# All-in-one_Starter_Kit_for_Arduino_Nano_.net
KiCad netlist of a schematic drawn in EAGLE
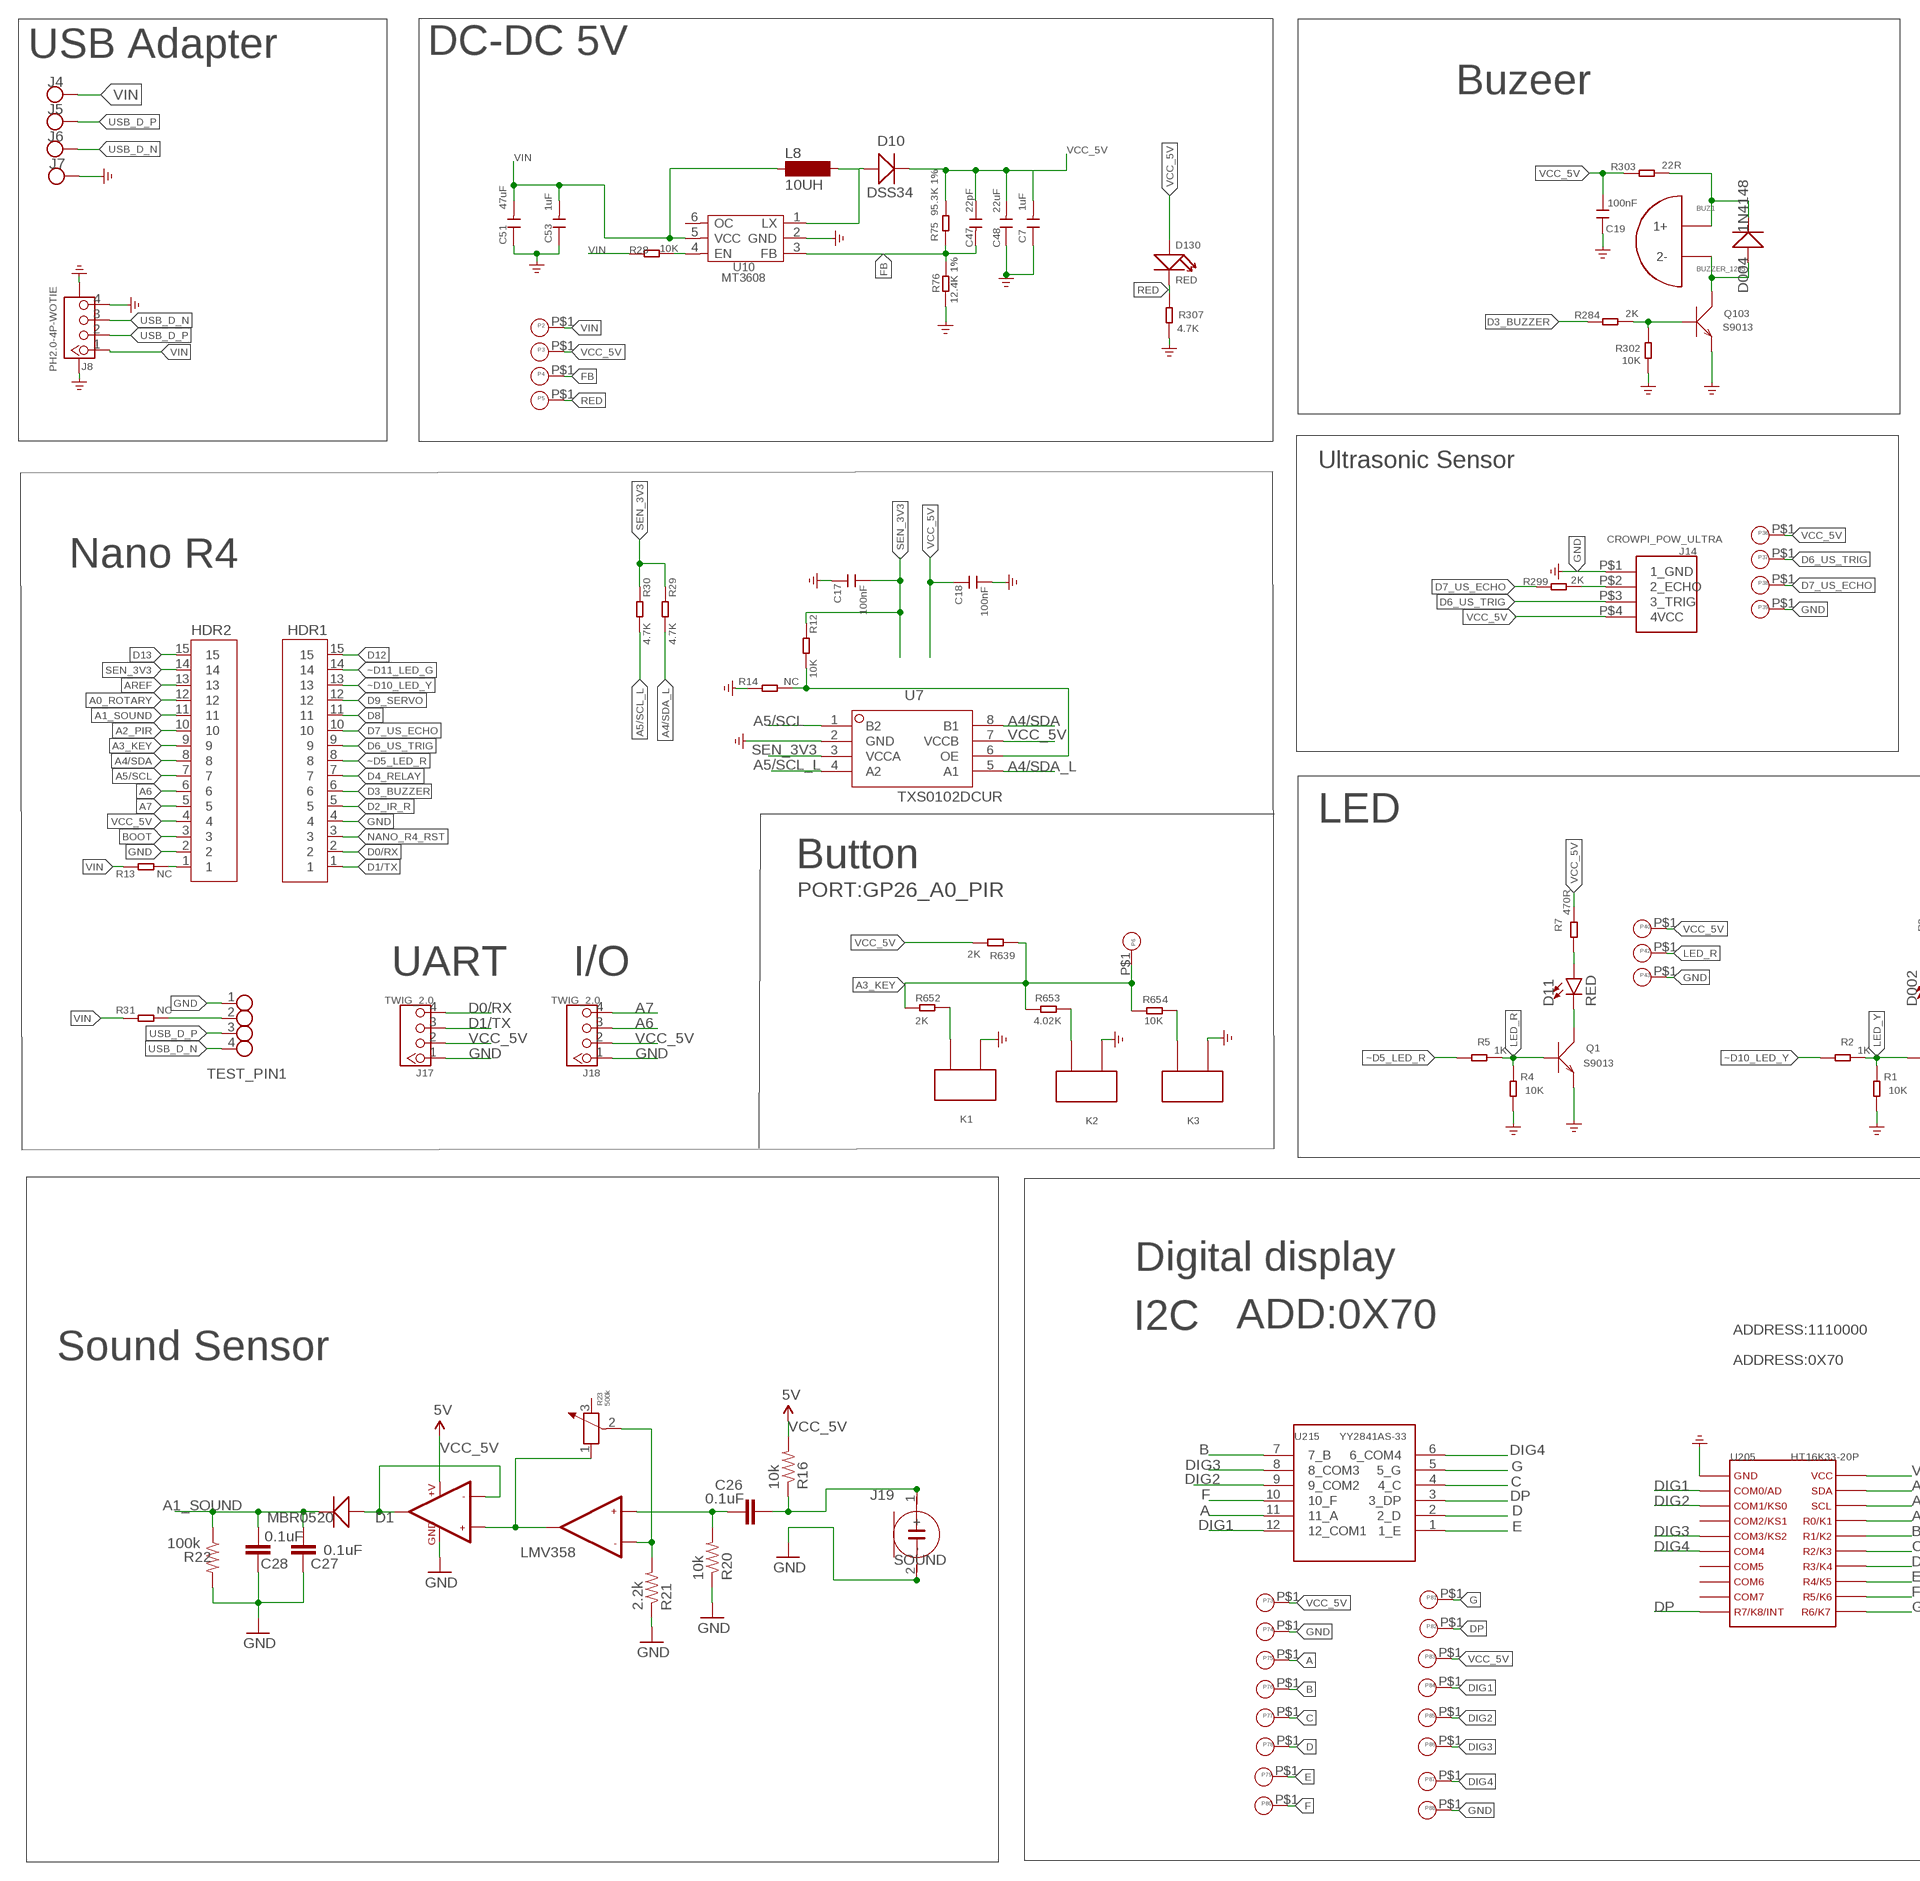
[diagram p0: schematic, sheet 1, part 1 of 2]
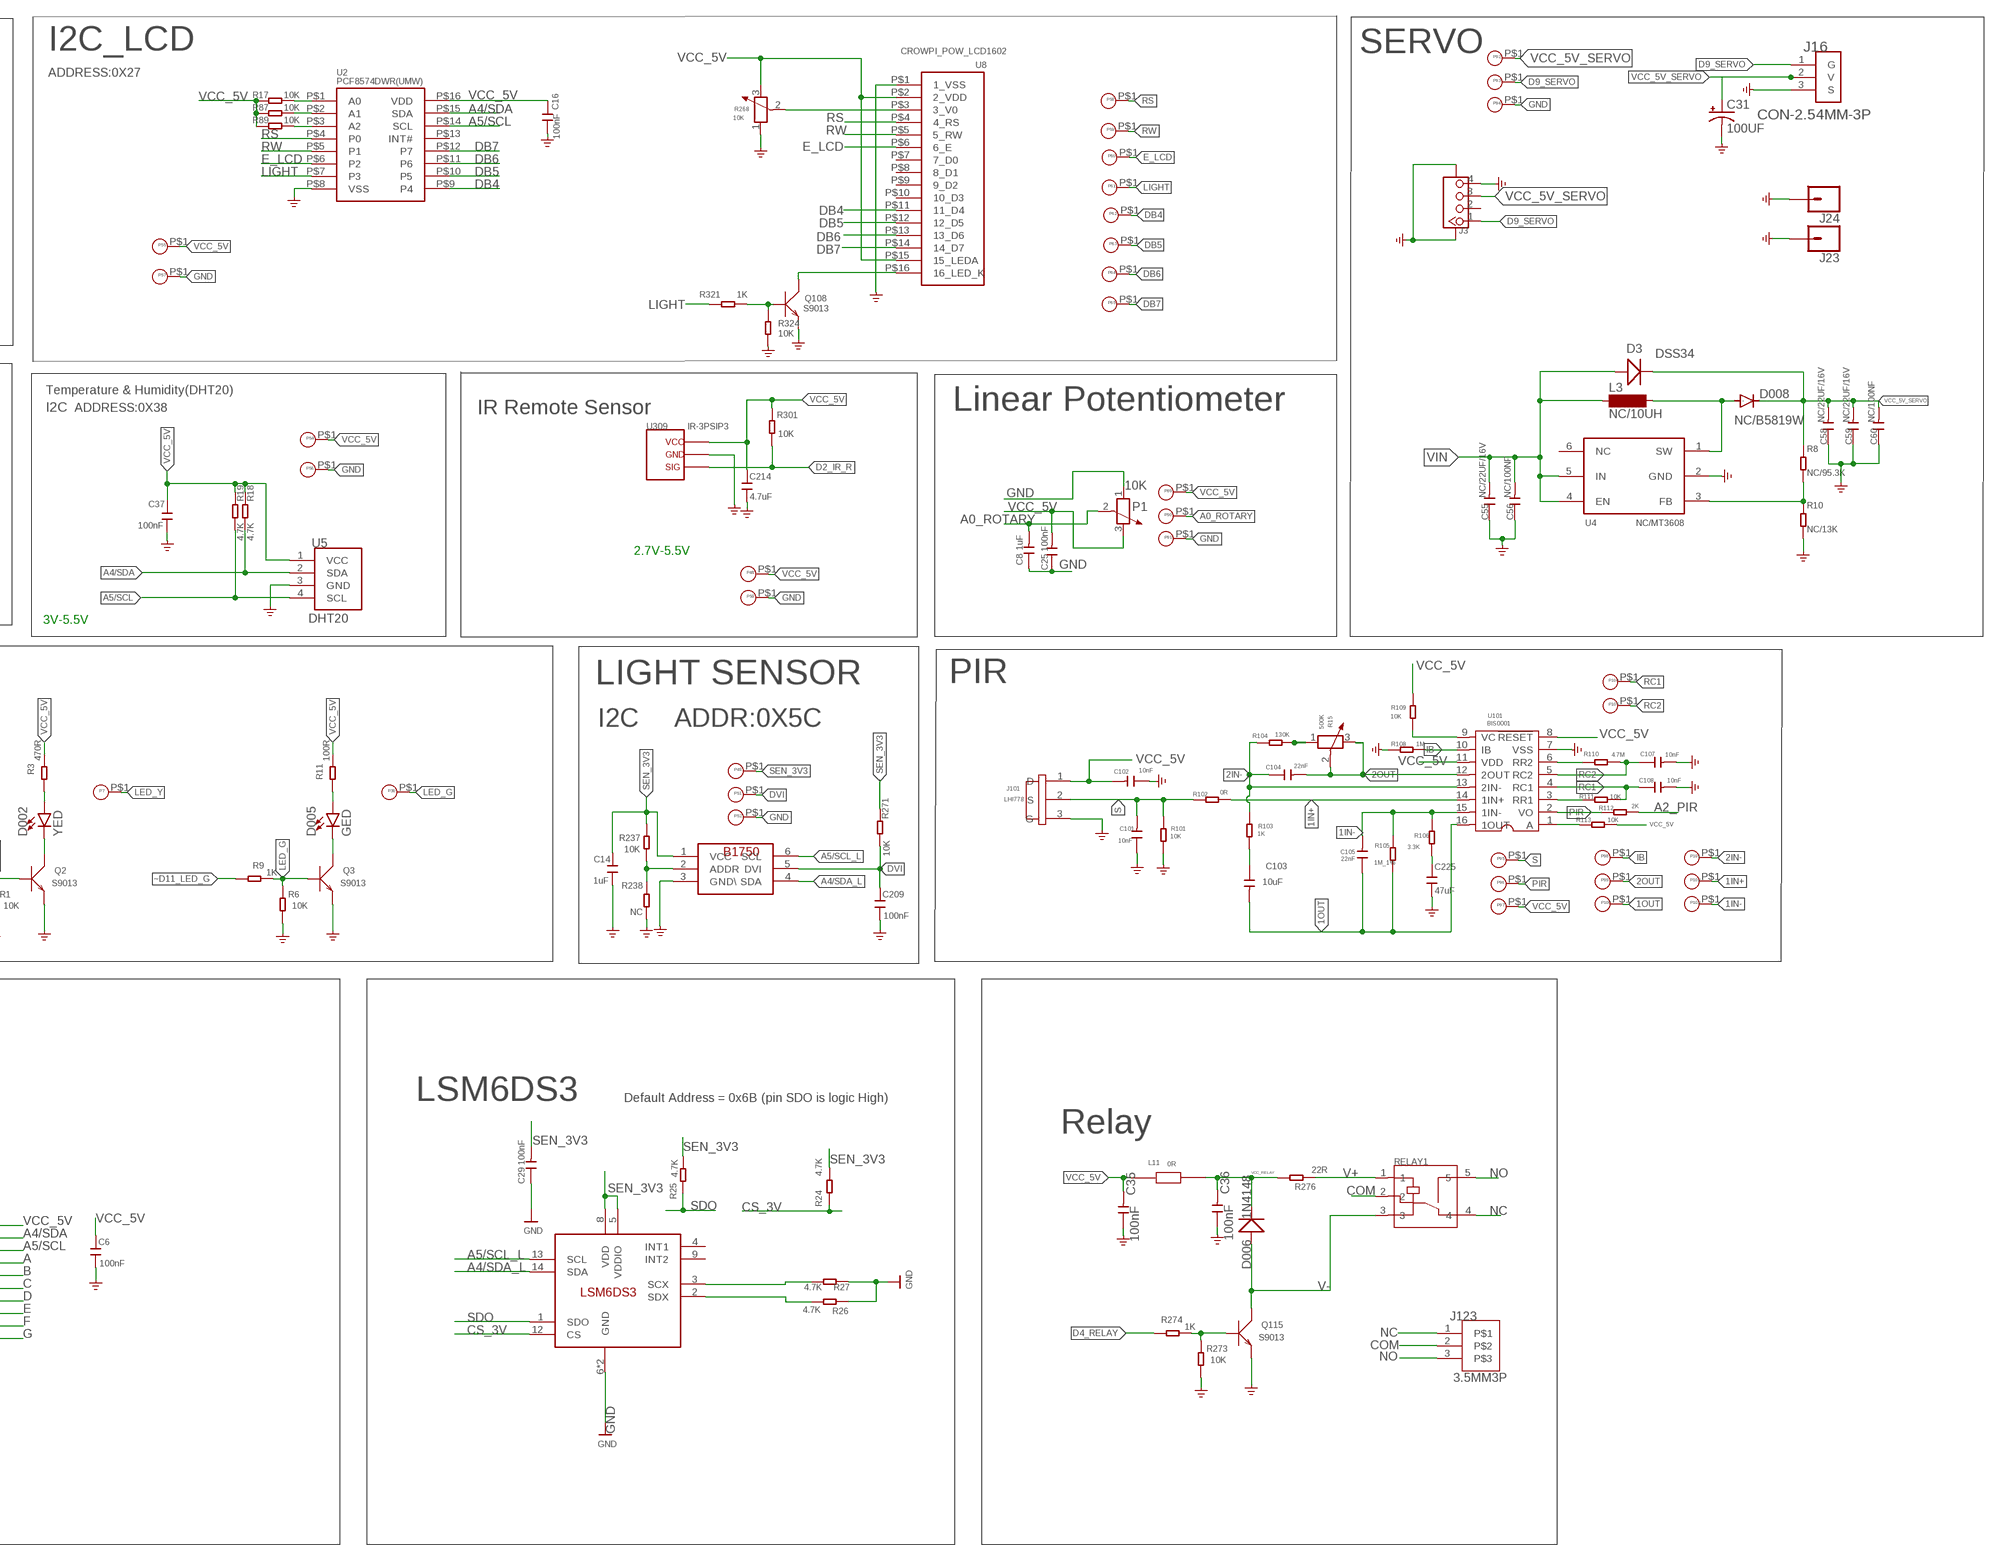
[diagram p1: schematic, sheet 1, part 2 of 2]

(export (version "E")
  (design (tool "Eeschema 10.0.6"))
  (components
    (comp (ref "BUZ1")
      (value "BUZZER_1295")
      (footprint "eagle-import:BUZZER-D12MM-DIP2")
      (libsource (lib "eagle-import") (part "BUZZERBUZZER_1295_DIP"))
    )
    (comp (ref "C6")
      (value "100nF")
      (footprint "eagle-import:0603")
      (libsource (lib "eagle-import") (part "cooper_C0603"))
    )
    (comp (ref "C7")
      (value "1uF")
      (footprint "eagle-import:C0603")
      (libsource (lib "eagle-import") (part "CAP"))
    )
    (comp (ref "C8")
      (value "1uF")
      (footprint "eagle-import:C0603")
      (libsource (lib "eagle-import") (part "C-0603"))
    )
    (comp (ref "C14")
      (value "1uF")
      (footprint "eagle-import:0603")
      (libsource (lib "eagle-import") (part "cooper_C0603"))
    )
    (comp (ref "C16")
      (value "100nF")
      (footprint "eagle-import:0603")
      (libsource (lib "eagle-import") (part "cooper_C0603"))
    )
    (comp (ref "C17")
      (value "100nF")
      (footprint "eagle-import:0603")
      (libsource (lib "eagle-import") (part "cooper_C0603"))
    )
    (comp (ref "C18")
      (value "100nF")
      (footprint "eagle-import:0603")
      (libsource (lib "eagle-import") (part "cooper_C0603"))
    )
    (comp (ref "C19")
      (value "100nF")
      (footprint "eagle-import:0603")
      (libsource (lib "eagle-import") (part "cooper_C0603"))
    )
    (comp (ref "C25")
      (value "100nF")
      (footprint "eagle-import:C0603")
      (libsource (lib "eagle-import") (part "C-0603"))
    )
    (comp (ref "C26")
      (value "0.1uF")
      (footprint "eagle-import:0603-CAP")
      (libsource (lib "eagle-import") (part "CAP0603-CAP"))
    )
    (comp (ref "C27")
      (value "0.1uF")
      (footprint "eagle-import:0603-CAP")
      (libsource (lib "eagle-import") (part "CAP0603-CAP"))
    )
    (comp (ref "C28")
      (value "0.1uF")
      (footprint "eagle-import:0603-CAP")
      (libsource (lib "eagle-import") (part "CAP0603-CAP"))
    )
    (comp (ref "C29")
      (value "100nF")
      (footprint "eagle-import:C0603")
      (libsource (lib "eagle-import") (part "C-0603"))
    )
    (comp (ref "C31")
      (value "100UF")
      (footprint "eagle-import:SANYO-OSCON_SMD_C6")
      (libsource (lib "eagle-import") (part "CPOL-USSANYO_SMD_C6"))
    )
    (comp (ref "C35")
      (value "100nF")
      (footprint "eagle-import:C0603")
      (libsource (lib "eagle-import") (part "C-0603"))
    )
    (comp (ref "C36")
      (value "100nF")
      (footprint "eagle-import:C0603")
      (libsource (lib "eagle-import") (part "C-0603"))
    )
    (comp (ref "C37")
      (value "100nF")
      (footprint "eagle-import:0603")
      (libsource (lib "eagle-import") (part "cooper_C0603"))
    )
    (comp (ref "C47")
      (value "22pF")
      (footprint "eagle-import:C0603")
      (libsource (lib "eagle-import") (part "CAP"))
    )
    (comp (ref "C48")
      (value "22uF")
      (footprint "eagle-import:C0805")
      (libsource (lib "eagle-import") (part "CAPC0805"))
    )
    (comp (ref "C51")
      (value "47uF")
      (footprint "eagle-import:C0805")
      (libsource (lib "eagle-import") (part "CAPC0805"))
    )
    (comp (ref "C53")
      (value "1uF")
      (footprint "eagle-import:C0603")
      (libsource (lib "eagle-import") (part "CAP"))
    )
    (comp (ref "C55")
      (value "NC/22UF/16V")
      (footprint "eagle-import:C0603")
      (libsource (lib "eagle-import") (part "SX1302_Module_CAP"))
    )
    (comp (ref "C56")
      (value "NC/100NF")
      (footprint "eagle-import:C0603")
      (libsource (lib "eagle-import") (part "SX1302_Module_CAP"))
    )
    (comp (ref "C58")
      (value "NC/22UF/16V")
      (footprint "eagle-import:C0603")
      (libsource (lib "eagle-import") (part "SX1302_Module_CAP"))
    )
    (comp (ref "C59")
      (value "NC/22UF/16V")
      (footprint "eagle-import:C0603")
      (libsource (lib "eagle-import") (part "SX1302_Module_CAP"))
    )
    (comp (ref "C60")
      (value "NC/100NF")
      (footprint "eagle-import:C0603")
      (libsource (lib "eagle-import") (part "SX1302_Module_CAP"))
    )
    (comp (ref "C101")
      (value "10nF")
      (footprint "eagle-import:C0603")
      (libsource (lib "eagle-import") (part "C-0603"))
    )
    (comp (ref "C102")
      (value "10nF")
      (footprint "eagle-import:C0603")
      (libsource (lib "eagle-import") (part "C-0603"))
    )
    (comp (ref "C103")
      (value "10uF")
      (footprint "eagle-import:0603")
      (libsource (lib "eagle-import") (part "C0603"))
    )
    (comp (ref "C104")
      (value "22nF")
      (footprint "eagle-import:C0603")
      (libsource (lib "eagle-import") (part "C-0603"))
    )
    (comp (ref "C105")
      (value "22nF")
      (footprint "eagle-import:C0603")
      (libsource (lib "eagle-import") (part "C-0603"))
    )
    (comp (ref "C107")
      (value "10nF")
      (footprint "eagle-import:C0603")
      (libsource (lib "eagle-import") (part "C-0603"))
    )
    (comp (ref "C108")
      (value "10nF")
      (footprint "eagle-import:C0603")
      (libsource (lib "eagle-import") (part "C-0603"))
    )
    (comp (ref "C209")
      (value "100nF")
      (footprint "eagle-import:0603")
      (libsource (lib "eagle-import") (part "cooper_C0603"))
    )
    (comp (ref "C214")
      (value "4.7uF")
      (footprint "eagle-import:0603")
      (libsource (lib "eagle-import") (part "cooper_C0603"))
    )
    (comp (ref "C225")
      (value "47uF")
      (footprint "eagle-import:0805")
      (libsource (lib "eagle-import") (part "C0805"))
    )
    (comp (ref "D1")
      (value "MBR0520")
      (footprint "eagle-import:SOD123-2.7X1.6")
      (libsource (lib "eagle-import") (part "D'MBR0520LT1'"))
    )
    (comp (ref "D002")
      (value "YED")
      (footprint "eagle-import:LED-8MM")
      (libsource (lib "eagle-import") (part "LED"))
    )
    (comp (ref "D3")
      (value "DSS34")
      (footprint "eagle-import:D_SOD123FL")
      (libsource (lib "eagle-import") (part "DIODE"))
    )
    (comp (ref "D004")
      (value "1N4148")
      (footprint "eagle-import:D_SOD123")
      (libsource (lib "eagle-import") (part "Crowtail_Starter_DIODE1206"))
    )
    (comp (ref "D005")
      (value "GED")
      (footprint "eagle-import:LED-8MM")
      (libsource (lib "eagle-import") (part "LED"))
    )
    (comp (ref "D006")
      (value "1N4148")
      (footprint "eagle-import:D_SOD123")
      (libsource (lib "eagle-import") (part "Crowtail_Starter_DIODE1206"))
    )
    (comp (ref "D008")
      (value "NC/B5819W")
      (footprint "eagle-import:SOD-123_MINI-SMA")
      (libsource (lib "eagle-import") (part "CGRM400-G1"))
    )
    (comp (ref "D10")
      (value "DSS34")
      (footprint "eagle-import:D_SOD123FL")
      (libsource (lib "eagle-import") (part "DIODE"))
    )
    (comp (ref "D11")
      (value "RED")
      (footprint "eagle-import:LED-8MM")
      (libsource (lib "eagle-import") (part "LED"))
    )
    (comp (ref "D130")
      (value "RED")
      (footprint "eagle-import:LED_0603_SMT")
      (libsource (lib "eagle-import") (part "LED_0603_SMT"))
    )
    (comp (ref "HDR1")
      (value "KH-2.54FH-1X15P-H8.5")
      (footprint "eagle-import:HDR-TH_15P-P2.54-V-F")
      (libsource (lib "eagle-import") (part "KH-2.54FH-1X15P-H8.5"))
    )
    (comp (ref "HDR2")
      (value "KH-2.54FH-1X15P-H8.5")
      (footprint "eagle-import:HDR-TH_15P-P2.54-V-F")
      (libsource (lib "eagle-import") (part "KH-2.54FH-1X15P-H8.5"))
    )
    (comp (ref "J3")
      (value "A_XBJ_CONNECTOR_TWIG-4P-2.0-SMD-FEMALE-REINFORCE90D")
      (footprint "eagle-import:A_XBJ_CONNECTOR_4P-SMD-2.0-90D")
      (libsource (lib "eagle-import") (part "A_XBJ_CONNECTOR_TWIG-4P-2.0-SMD-FEMALE-REINFORCE90D"))
    )
    (comp (ref "J4")
      (value "TP-SMDTP-SMD-2X4MM")
      (footprint "eagle-import:TP-SMD-2X4MM")
      (libsource (lib "eagle-import") (part "TP-SMDTP-SMD-2X4MM"))
    )
    (comp (ref "J5")
      (value "TP-SMDTP-SMD-2X4MM")
      (footprint "eagle-import:TP-SMD-2X4MM")
      (libsource (lib "eagle-import") (part "TP-SMDTP-SMD-2X4MM"))
    )
    (comp (ref "J6")
      (value "TP-SMDTP-SMD-2X4MM")
      (footprint "eagle-import:TP-SMD-2X4MM")
      (libsource (lib "eagle-import") (part "TP-SMDTP-SMD-2X4MM"))
    )
    (comp (ref "J7")
      (value "TP-SMDTP-SMD-2X4MM")
      (footprint "eagle-import:TP-SMD-2X4MM")
      (libsource (lib "eagle-import") (part "TP-SMDTP-SMD-2X4MM"))
    )
    (comp (ref "J8")
      (value "PH2.0-4P-WOTIE")
      (footprint "eagle-import:PH2.0-4P")
      (libsource (lib "eagle-import") (part "PH2.0-4P-WOTIE"))
    )
    (comp (ref "J14")
      (value "CROWPI_POW_ULTRA")
      (footprint "eagle-import:CROWPI_POW_ULTRA")
      (libsource (lib "eagle-import") (part "CROWPI_POW_ULTRA"))
    )
    (comp (ref "J16")
      (value "CON-2.54MM-3P")
      (footprint "eagle-import:CON-PZ-2.54MM-1_3P-WT")
      (libsource (lib "eagle-import") (part "CON-2.54MM-13P-WT-SG90"))
    )
    (comp (ref "J17")
      (value "TWIG_2.0")
      (footprint "eagle-import:2.0_1X4")
      (libsource (lib "eagle-import") (part "TWIG_2.0"))
    )
    (comp (ref "J18")
      (value "TWIG_2.0")
      (footprint "eagle-import:2.0_1X4")
      (libsource (lib "eagle-import") (part "TWIG_2.0"))
    )
    (comp (ref "J19")
      (value "SOUND")
      (footprint "eagle-import:TEMPLATE_2P-D8.9MM")
      (libsource (lib "eagle-import") (part "TEMPLATE_MICROPHONE"))
    )
    (comp (ref "J23")
      (value "CONN_01_2.6MM1X01_2.6-4MM")
      (footprint "eagle-import:1X01_2.6MM")
      (libsource (lib "eagle-import") (part "CONN_01_2.6MM1X01_2.6-4MM"))
    )
    (comp (ref "J24")
      (value "CONN_01_2.6MM1X01_2.6-4MM")
      (footprint "eagle-import:1X01_2.6MM")
      (libsource (lib "eagle-import") (part "CONN_01_2.6MM1X01_2.6-4MM"))
    )
    (comp (ref "J101")
      (value "LHI778")
      (footprint "eagle-import:3P-D8.1MM")
      (libsource (lib "eagle-import") (part "LHI778"))
    )
    (comp (ref "J123")
      (value "3.5MM3P")
      (footprint "eagle-import:3.5MM_3P")
      (libsource (lib "eagle-import") (part "3.5MM3P"))
    )
    (comp (ref "K1")
      (value "BUTTON_2P")
      (footprint "eagle-import:BUTTON_2P")
      (libsource (lib "eagle-import") (part "BUTTON_2P"))
    )
    (comp (ref "K2")
      (value "BUTTON_2P")
      (footprint "eagle-import:BUTTON_2P")
      (libsource (lib "eagle-import") (part "BUTTON_2P"))
    )
    (comp (ref "K3")
      (value "BUTTON_2P")
      (footprint "eagle-import:BUTTON_2P")
      (libsource (lib "eagle-import") (part "BUTTON_2P"))
    )
    (comp (ref "L3")
      (value "NC/10UH")
      (footprint "eagle-import:MS42")
      (libsource (lib "eagle-import") (part "MS42"))
    )
    (comp (ref "L8")
      (value "10UH")
      (footprint "eagle-import:MS42")
      (libsource (lib "eagle-import") (part "MS42"))
    )
    (comp (ref "L11")
      (value "0R")
      (footprint "eagle-import:201209")
      (libsource (lib "eagle-import") (part "CMP201209UD1R0MT201209"))
    )
    (comp (ref "P1")
      (value "10K")
      (footprint "eagle-import:3P-SQUA-45.6X10X5.8H")
      (libsource (lib "eagle-import") (part "R-POTENTIOMETER"))
    )
    (comp (ref "P2")
      (value "PADPAD-1.0MM")
      (footprint "eagle-import:PAD-1.0MM")
      (libsource (lib "eagle-import") (part "PADPAD-1.0MM"))
    )
    (comp (ref "P3")
      (value "PADPAD-1.0MM")
      (footprint "eagle-import:PAD-1.0MM")
      (libsource (lib "eagle-import") (part "PADPAD-1.0MM"))
    )
    (comp (ref "P4")
      (value "PADPAD-1.0MM")
      (footprint "eagle-import:PAD-1.0MM")
      (libsource (lib "eagle-import") (part "PADPAD-1.0MM"))
    )
    (comp (ref "P5")
      (value "PADPAD-1.0MM")
      (footprint "eagle-import:PAD-1.0MM")
      (libsource (lib "eagle-import") (part "PADPAD-1.0MM"))
    )
    (comp (ref "P6")
      (value "PADPAD-1.0MM")
      (footprint "eagle-import:PAD-1.0MM")
      (libsource (lib "eagle-import") (part "PADPAD-1.0MM"))
    )
    (comp (ref "P7")
      (value "PADPAD-1.0MM")
      (footprint "eagle-import:PAD-1.0MM")
      (libsource (lib "eagle-import") (part "PADPAD-1.0MM"))
    )
    (comp (ref "P30")
      (value "PADPAD-1.0MM")
      (footprint "eagle-import:PAD-1.0MM")
      (libsource (lib "eagle-import") (part "PADPAD-1.0MM"))
    )
    (comp (ref "P36")
      (value "PADPAD-1.0MM")
      (footprint "eagle-import:PAD-1.0MM")
      (libsource (lib "eagle-import") (part "PADPAD-1.0MM"))
    )
    (comp (ref "P37")
      (value "PADPAD-1.0MM")
      (footprint "eagle-import:PAD-1.0MM")
      (libsource (lib "eagle-import") (part "PADPAD-1.0MM"))
    )
    (comp (ref "P38")
      (value "PADPAD-1.0MM")
      (footprint "eagle-import:PAD-1.0MM")
      (libsource (lib "eagle-import") (part "PADPAD-1.0MM"))
    )
    (comp (ref "P39")
      (value "PADPAD-1.0MM")
      (footprint "eagle-import:PAD-1.0MM")
      (libsource (lib "eagle-import") (part "PADPAD-1.0MM"))
    )
    (comp (ref "P40")
      (value "PADPAD-1.0MM")
      (footprint "eagle-import:PAD-1.0MM")
      (libsource (lib "eagle-import") (part "PADPAD-1.0MM"))
    )
    (comp (ref "P42")
      (value "PADPAD-1.0MM")
      (footprint "eagle-import:PAD-1.0MM")
      (libsource (lib "eagle-import") (part "PADPAD-1.0MM"))
    )
    (comp (ref "P43")
      (value "PADPAD-1.0MM")
      (footprint "eagle-import:PAD-1.0MM")
      (libsource (lib "eagle-import") (part "PADPAD-1.0MM"))
    )
    (comp (ref "P48")
      (value "PADPAD-1.0MM")
      (footprint "eagle-import:PAD-1.0MM")
      (libsource (lib "eagle-import") (part "PADPAD-1.0MM"))
    )
    (comp (ref "P49")
      (value "PADPAD-1.0MM")
      (footprint "eagle-import:PAD-1.0MM")
      (libsource (lib "eagle-import") (part "PADPAD-1.0MM"))
    )
    (comp (ref "P50")
      (value "PADPAD-1.0MM")
      (footprint "eagle-import:PAD-1.0MM")
      (libsource (lib "eagle-import") (part "PADPAD-1.0MM"))
    )
    (comp (ref "P51")
      (value "PADPAD-1.0MM")
      (footprint "eagle-import:PAD-1.0MM")
      (libsource (lib "eagle-import") (part "PADPAD-1.0MM"))
    )
    (comp (ref "P52")
      (value "PADPAD-1.0MM")
      (footprint "eagle-import:PAD-1.0MM")
      (libsource (lib "eagle-import") (part "PADPAD-1.0MM"))
    )
    (comp (ref "P54")
      (value "PADPAD-1.0MM")
      (footprint "eagle-import:PAD-1.0MM")
      (libsource (lib "eagle-import") (part "PADPAD-1.0MM"))
    )
    (comp (ref "P55")
      (value "PADPAD-1.0MM")
      (footprint "eagle-import:PAD-1.0MM")
      (libsource (lib "eagle-import") (part "PADPAD-1.0MM"))
    )
    (comp (ref "P56")
      (value "PADPAD-1.0MM")
      (footprint "eagle-import:PAD-1.0MM")
      (libsource (lib "eagle-import") (part "PADPAD-1.0MM"))
    )
    (comp (ref "P57")
      (value "PADPAD-1.0MM")
      (footprint "eagle-import:PAD-1.0MM")
      (libsource (lib "eagle-import") (part "PADPAD-1.0MM"))
    )
    (comp (ref "P58")
      (value "PADPAD-1.0MM")
      (footprint "eagle-import:PAD-1.0MM")
      (libsource (lib "eagle-import") (part "PADPAD-1.0MM"))
    )
    (comp (ref "P59")
      (value "PADPAD-1.0MM")
      (footprint "eagle-import:PAD-1.0MM")
      (libsource (lib "eagle-import") (part "PADPAD-1.0MM"))
    )
    (comp (ref "P60")
      (value "PADPAD-1.0MM")
      (footprint "eagle-import:PAD-1.0MM")
      (libsource (lib "eagle-import") (part "PADPAD-1.0MM"))
    )
    (comp (ref "P61")
      (value "PADPAD-1.0MM")
      (footprint "eagle-import:PAD-1.0MM")
      (libsource (lib "eagle-import") (part "PADPAD-1.0MM"))
    )
    (comp (ref "P62")
      (value "PADPAD-1.0MM")
      (footprint "eagle-import:PAD-1.0MM")
      (libsource (lib "eagle-import") (part "PADPAD-1.0MM"))
    )
    (comp (ref "P63")
      (value "PADPAD-1.0MM")
      (footprint "eagle-import:PAD-1.0MM")
      (libsource (lib "eagle-import") (part "PADPAD-1.0MM"))
    )
    (comp (ref "P64")
      (value "PADPAD-1.0MM")
      (footprint "eagle-import:PAD-1.0MM")
      (libsource (lib "eagle-import") (part "PADPAD-1.0MM"))
    )
    (comp (ref "P65")
      (value "PADPAD-1.0MM")
      (footprint "eagle-import:PAD-1.0MM")
      (libsource (lib "eagle-import") (part "PADPAD-1.0MM"))
    )
    (comp (ref "P73")
      (value "PADPAD-1.0MM")
      (footprint "eagle-import:PAD-1.0MM")
      (libsource (lib "eagle-import") (part "PADPAD-1.0MM"))
    )
    (comp (ref "P74")
      (value "PADPAD-1.0MM")
      (footprint "eagle-import:PAD-1.0MM")
      (libsource (lib "eagle-import") (part "PADPAD-1.0MM"))
    )
    (comp (ref "P75")
      (value "PADPAD-1.0MM")
      (footprint "eagle-import:PAD-1.0MM")
      (libsource (lib "eagle-import") (part "PADPAD-1.0MM"))
    )
    (comp (ref "P76")
      (value "PADPAD-1.0MM")
      (footprint "eagle-import:PAD-1.0MM")
      (libsource (lib "eagle-import") (part "PADPAD-1.0MM"))
    )
    (comp (ref "P77")
      (value "PADPAD-1.0MM")
      (footprint "eagle-import:PAD-1.0MM")
      (libsource (lib "eagle-import") (part "PADPAD-1.0MM"))
    )
    (comp (ref "P78")
      (value "PADPAD-1.0MM")
      (footprint "eagle-import:PAD-1.0MM")
      (libsource (lib "eagle-import") (part "PADPAD-1.0MM"))
    )
    (comp (ref "P79")
      (value "PADPAD-1.0MM")
      (footprint "eagle-import:PAD-1.0MM")
      (libsource (lib "eagle-import") (part "PADPAD-1.0MM"))
    )
    (comp (ref "P80")
      (value "PADPAD-1.0MM")
      (footprint "eagle-import:PAD-1.0MM")
      (libsource (lib "eagle-import") (part "PADPAD-1.0MM"))
    )
    (comp (ref "P81")
      (value "PADPAD-1.0MM")
      (footprint "eagle-import:PAD-1.0MM")
      (libsource (lib "eagle-import") (part "PADPAD-1.0MM"))
    )
    (comp (ref "P82")
      (value "PADPAD-1.0MM")
      (footprint "eagle-import:PAD-1.0MM")
      (libsource (lib "eagle-import") (part "PADPAD-1.0MM"))
    )
    (comp (ref "P83")
      (value "PADPAD-1.0MM")
      (footprint "eagle-import:PAD-1.0MM")
      (libsource (lib "eagle-import") (part "PADPAD-1.0MM"))
    )
    (comp (ref "P84")
      (value "PADPAD-1.0MM")
      (footprint "eagle-import:PAD-1.0MM")
      (libsource (lib "eagle-import") (part "PADPAD-1.0MM"))
    )
    (comp (ref "P85")
      (value "PADPAD-1.0MM")
      (footprint "eagle-import:PAD-1.0MM")
      (libsource (lib "eagle-import") (part "PADPAD-1.0MM"))
    )
    (comp (ref "P86")
      (value "PADPAD-1.0MM")
      (footprint "eagle-import:PAD-1.0MM")
      (libsource (lib "eagle-import") (part "PADPAD-1.0MM"))
    )
    (comp (ref "P87")
      (value "PADPAD-1.0MM")
      (footprint "eagle-import:PAD-1.0MM")
      (libsource (lib "eagle-import") (part "PADPAD-1.0MM"))
    )
    (comp (ref "P88")
      (value "PADPAD-1.0MM")
      (footprint "eagle-import:PAD-1.0MM")
      (libsource (lib "eagle-import") (part "PADPAD-1.0MM"))
    )
    (comp (ref "P89")
      (value "PADPAD-1.0MM")
      (footprint "eagle-import:PAD-1.0MM")
      (libsource (lib "eagle-import") (part "PADPAD-1.0MM"))
    )
    (comp (ref "P90")
      (value "PADPAD-1.0MM")
      (footprint "eagle-import:PAD-1.0MM")
      (libsource (lib "eagle-import") (part "PADPAD-1.0MM"))
    )
    (comp (ref "P91")
      (value "PADPAD-1.0MM")
      (footprint "eagle-import:PAD-1.0MM")
      (libsource (lib "eagle-import") (part "PADPAD-1.0MM"))
    )
    (comp (ref "P92")
      (value "PADPAD-1.0MM")
      (footprint "eagle-import:PAD-1.0MM")
      (libsource (lib "eagle-import") (part "PADPAD-1.0MM"))
    )
    (comp (ref "P93")
      (value "PADPAD-1.0MM")
      (footprint "eagle-import:PAD-1.0MM")
      (libsource (lib "eagle-import") (part "PADPAD-1.0MM"))
    )
    (comp (ref "P94")
      (value "PADPAD-1.0MM")
      (footprint "eagle-import:PAD-1.0MM")
      (libsource (lib "eagle-import") (part "PADPAD-1.0MM"))
    )
    (comp (ref "P95")
      (value "PADPAD-1.0MM")
      (footprint "eagle-import:PAD-1.0MM")
      (libsource (lib "eagle-import") (part "PADPAD-1.0MM"))
    )
    (comp (ref "P96")
      (value "PADPAD-1.0MM")
      (footprint "eagle-import:PAD-1.0MM")
      (libsource (lib "eagle-import") (part "PADPAD-1.0MM"))
    )
    (comp (ref "P97")
      (value "PADPAD-1.0MM")
      (footprint "eagle-import:PAD-1.0MM")
      (libsource (lib "eagle-import") (part "PADPAD-1.0MM"))
    )
    (comp (ref "P98")
      (value "PADPAD-1.0MM")
      (footprint "eagle-import:PAD-1.0MM")
      (libsource (lib "eagle-import") (part "PADPAD-1.0MM"))
    )
    (comp (ref "P99")
      (value "PADPAD-1.0MM")
      (footprint "eagle-import:PAD-1.0MM")
      (libsource (lib "eagle-import") (part "PADPAD-1.0MM"))
    )
    (comp (ref "P100")
      (value "PADPAD-1.0MM")
      (footprint "eagle-import:PAD-1.0MM")
      (libsource (lib "eagle-import") (part "PADPAD-1.0MM"))
    )
    (comp (ref "P101")
      (value "PADPAD-1.0MM")
      (footprint "eagle-import:PAD-1.0MM")
      (libsource (lib "eagle-import") (part "PADPAD-1.0MM"))
    )
    (comp (ref "P102")
      (value "PADPAD-1.0MM")
      (footprint "eagle-import:PAD-1.0MM")
      (libsource (lib "eagle-import") (part "PADPAD-1.0MM"))
    )
    (comp (ref "P103")
      (value "PADPAD-1.0MM")
      (footprint "eagle-import:PAD-1.0MM")
      (libsource (lib "eagle-import") (part "PADPAD-1.0MM"))
    )
    (comp (ref "P104")
      (value "PADPAD-1.0MM")
      (footprint "eagle-import:PAD-1.0MM")
      (libsource (lib "eagle-import") (part "PADPAD-1.0MM"))
    )
    (comp (ref "P105")
      (value "PADPAD-1.0MM")
      (footprint "eagle-import:PAD-1.0MM")
      (libsource (lib "eagle-import") (part "PADPAD-1.0MM"))
    )
    (comp (ref "Q1")
      (value "S9013")
      (footprint "eagle-import:SOT23@1")
      (libsource (lib "eagle-import") (part "TRANSISTOR-NPN-SOT23"))
    )
    (comp (ref "Q2")
      (value "S9013")
      (footprint "eagle-import:SOT23@1")
      (libsource (lib "eagle-import") (part "TRANSISTOR-NPN-SOT23"))
    )
    (comp (ref "Q3")
      (value "S9013")
      (footprint "eagle-import:SOT23@1")
      (libsource (lib "eagle-import") (part "TRANSISTOR-NPN-SOT23"))
    )
    (comp (ref "Q103")
      (value "S9013")
      (footprint "eagle-import:SOT23@1")
      (libsource (lib "eagle-import") (part "TRANSISTOR-NPN-SOT23"))
    )
    (comp (ref "Q108")
      (value "S9013")
      (footprint "eagle-import:SOT23@1")
      (libsource (lib "eagle-import") (part "TRANSISTOR-NPN-SOT23"))
    )
    (comp (ref "Q115")
      (value "S9013")
      (footprint "eagle-import:SOT23@1")
      (libsource (lib "eagle-import") (part "TRANSISTOR-NPN-SOT23"))
    )
    (comp (ref "R1")
      (value "10K")
      (footprint "eagle-import:R0603")
      (libsource (lib "eagle-import") (part "R-0603"))
    )
    (comp (ref "R2")
      (value "1K")
      (footprint "eagle-import:R0603")
      (libsource (lib "eagle-import") (part "R-0603"))
    )
    (comp (ref "R3")
      (value "470R")
      (footprint "eagle-import:R0603")
      (libsource (lib "eagle-import") (part "R-0603"))
    )
    (comp (ref "R4")
      (value "10K")
      (footprint "eagle-import:R0603")
      (libsource (lib "eagle-import") (part "R-0603"))
    )
    (comp (ref "R5")
      (value "1K")
      (footprint "eagle-import:R0603")
      (libsource (lib "eagle-import") (part "R-0603"))
    )
    (comp (ref "R6")
      (value "10K")
      (footprint "eagle-import:R0603")
      (libsource (lib "eagle-import") (part "R-0603"))
    )
    (comp (ref "R7")
      (value "470R")
      (footprint "eagle-import:R0603")
      (libsource (lib "eagle-import") (part "R-0603"))
    )
    (comp (ref "R8")
      (value "NC/95.3K")
      (footprint "eagle-import:R0603")
      (libsource (lib "eagle-import") (part "RESR0603"))
    )
    (comp (ref "R9")
      (value "1K")
      (footprint "eagle-import:R0603")
      (libsource (lib "eagle-import") (part "R-0603"))
    )
    (comp (ref "R10")
      (value "NC/13K")
      (footprint "eagle-import:R0603")
      (libsource (lib "eagle-import") (part "RESR0603"))
    )
    (comp (ref "R11")
      (value "100R")
      (footprint "eagle-import:R0603")
      (libsource (lib "eagle-import") (part "R-0603"))
    )
    (comp (ref "R12")
      (value "10K")
      (footprint "eagle-import:R0603")
      (libsource (lib "eagle-import") (part "R0603"))
    )
    (comp (ref "R13")
      (value "NC")
      (footprint "eagle-import:R0603")
      (libsource (lib "eagle-import") (part "R0603"))
    )
    (comp (ref "R14")
      (value "NC")
      (footprint "eagle-import:R0603")
      (libsource (lib "eagle-import") (part "R0603"))
    )
    (comp (ref "R15")
      (value "500K")
      (footprint "eagle-import:3P-SMD-SQUA-3.6X3.3")
      (libsource (lib "eagle-import") (part "R-POTENTIOMETER-SMD"))
    )
    (comp (ref "R16")
      (value "10k")
      (footprint "eagle-import:0603-RES")
      (libsource (lib "eagle-import") (part "RESISTOR0603-RES"))
    )
    (comp (ref "R17")
      (value "10K")
      (footprint "eagle-import:R0603")
      (libsource (lib "eagle-import") (part "R0603"))
    )
    (comp (ref "R18")
      (value "4.7K")
      (footprint "eagle-import:R0603")
      (libsource (lib "eagle-import") (part "R0603"))
    )
    (comp (ref "R19")
      (value "4.7K")
      (footprint "eagle-import:R0603")
      (libsource (lib "eagle-import") (part "R0603"))
    )
    (comp (ref "R20")
      (value "10k")
      (footprint "eagle-import:0603-RES")
      (libsource (lib "eagle-import") (part "RESISTOR0603-RES"))
    )
    (comp (ref "R21")
      (value "2.2k")
      (footprint "eagle-import:0603-RES")
      (libsource (lib "eagle-import") (part "RESISTOR0603-RES"))
    )
    (comp (ref "R22")
      (value "100k")
      (footprint "eagle-import:0603-RES")
      (libsource (lib "eagle-import") (part "RESISTOR0603-RES"))
    )
    (comp (ref "R23")
      (value "500k")
      (footprint "eagle-import:3P-SMD-SQUA-3.6X3.3")
      (libsource (lib "eagle-import") (part "R-POTENTIOMETER-SMD"))
    )
    (comp (ref "R24")
      (value "4.7K")
      (footprint "eagle-import:R0603")
      (libsource (lib "eagle-import") (part "R-0603"))
    )
    (comp (ref "R25")
      (value "4.7K")
      (footprint "eagle-import:R0603")
      (libsource (lib "eagle-import") (part "R-0603"))
    )
    (comp (ref "R26")
      (value "4.7K")
      (footprint "eagle-import:R0603")
      (libsource (lib "eagle-import") (part "R-0603"))
    )
    (comp (ref "R27")
      (value "4.7K")
      (footprint "eagle-import:R0603")
      (libsource (lib "eagle-import") (part "R-0603"))
    )
    (comp (ref "R28")
      (value "10K")
      (footprint "eagle-import:R0603-SP")
      (libsource (lib "eagle-import") (part "RES-0603"))
    )
    (comp (ref "R29")
      (value "4.7K")
      (footprint "eagle-import:R0603")
      (libsource (lib "eagle-import") (part "R0603"))
    )
    (comp (ref "R30")
      (value "4.7K")
      (footprint "eagle-import:R0603")
      (libsource (lib "eagle-import") (part "R0603"))
    )
    (comp (ref "R31")
      (value "NC")
      (footprint "eagle-import:R0603")
      (libsource (lib "eagle-import") (part "R0603"))
    )
    (comp (ref "R75")
      (value "95.3K 1%")
      (footprint "eagle-import:R0603-SP")
      (libsource (lib "eagle-import") (part "RES-0603"))
    )
    (comp (ref "R76")
      (value "12.4K 1%")
      (footprint "eagle-import:R0603-SP")
      (libsource (lib "eagle-import") (part "RES-0603"))
    )
    (comp (ref "R87")
      (value "10K")
      (footprint "eagle-import:R0603")
      (libsource (lib "eagle-import") (part "R0603"))
    )
    (comp (ref "R89")
      (value "10K")
      (footprint "eagle-import:R0603")
      (libsource (lib "eagle-import") (part "R0603"))
    )
    (comp (ref "R101")
      (value "10K")
      (footprint "eagle-import:R0603")
      (libsource (lib "eagle-import") (part "R-0603"))
    )
    (comp (ref "R102")
      (value "0R")
      (footprint "eagle-import:R0603")
      (libsource (lib "eagle-import") (part "R-0603"))
    )
    (comp (ref "R103")
      (value "1K")
      (footprint "eagle-import:R0603")
      (libsource (lib "eagle-import") (part "R-0603"))
    )
    (comp (ref "R104")
      (value "130K")
      (footprint "eagle-import:R0603")
      (libsource (lib "eagle-import") (part "R-0603"))
    )
    (comp (ref "R105")
      (value "1M_1%")
      (footprint "eagle-import:R0603")
      (libsource (lib "eagle-import") (part "R-0603"))
    )
    (comp (ref "R106")
      (value "3.3K")
      (footprint "eagle-import:R0603")
      (libsource (lib "eagle-import") (part "R-0603"))
    )
    (comp (ref "R108")
      (value "1M")
      (footprint "eagle-import:R0603")
      (libsource (lib "eagle-import") (part "R-0603"))
    )
    (comp (ref "R109")
      (value "10K")
      (footprint "eagle-import:R0603")
      (libsource (lib "eagle-import") (part "R-0603"))
    )
    (comp (ref "R110")
      (value "4.7M")
      (footprint "eagle-import:R0603")
      (libsource (lib "eagle-import") (part "R-0603"))
    )
    (comp (ref "R111")
      (value "10K")
      (footprint "eagle-import:R0603")
      (libsource (lib "eagle-import") (part "R-0603"))
    )
    (comp (ref "R112")
      (value "2K")
      (footprint "eagle-import:R0603")
      (libsource (lib "eagle-import") (part "R-0603"))
    )
    (comp (ref "R113")
      (value "10K")
      (footprint "eagle-import:R0603")
      (libsource (lib "eagle-import") (part "R-0603"))
    )
    (comp (ref "R237")
      (value "10K")
      (footprint "eagle-import:R0603")
      (libsource (lib "eagle-import") (part "R0603"))
    )
    (comp (ref "R238")
      (value "NC")
      (footprint "eagle-import:R0603")
      (libsource (lib "eagle-import") (part "R0603"))
    )
    (comp (ref "R268")
      (value "10K")
      (footprint "eagle-import:3P-SMD-SQUA-3.6X3.3")
      (libsource (lib "eagle-import") (part "R-POTENTIOMETER-SMD"))
    )
    (comp (ref "R271")
      (value "10K")
      (footprint "eagle-import:R0603")
      (libsource (lib "eagle-import") (part "R0603"))
    )
    (comp (ref "R273")
      (value "10K")
      (footprint "eagle-import:R0603")
      (libsource (lib "eagle-import") (part "R-0603"))
    )
    (comp (ref "R274")
      (value "1K")
      (footprint "eagle-import:R0603")
      (libsource (lib "eagle-import") (part "R-0603"))
    )
    (comp (ref "R276")
      (value "22R")
      (footprint "eagle-import:R0603")
      (libsource (lib "eagle-import") (part "R-0603"))
    )
    (comp (ref "R284")
      (value "2K")
      (footprint "eagle-import:R0603")
      (libsource (lib "eagle-import") (part "R0603"))
    )
    (comp (ref "R299")
      (value "2K")
      (footprint "eagle-import:R0603")
      (libsource (lib "eagle-import") (part "R0603"))
    )
    (comp (ref "R301")
      (value "10K")
      (footprint "eagle-import:R0603")
      (libsource (lib "eagle-import") (part "R0603"))
    )
    (comp (ref "R302")
      (value "10K")
      (footprint "eagle-import:R0603")
      (libsource (lib "eagle-import") (part "R0603"))
    )
    (comp (ref "R303")
      (value "22R")
      (footprint "eagle-import:R0603")
      (libsource (lib "eagle-import") (part "R0603"))
    )
    (comp (ref "R307")
      (value "4.7K")
      (footprint "eagle-import:R0603")
      (libsource (lib "eagle-import") (part "R0603"))
    )
    (comp (ref "R321")
      (value "1K")
      (footprint "eagle-import:R0603")
      (libsource (lib "eagle-import") (part "R0603"))
    )
    (comp (ref "R324")
      (value "10K")
      (footprint "eagle-import:R0603")
      (libsource (lib "eagle-import") (part "R0603"))
    )
    (comp (ref "R639")
      (value "2K")
      (footprint "eagle-import:R0603")
      (libsource (lib "eagle-import") (part "RESR0603"))
    )
    (comp (ref "R652")
      (value "2K")
      (footprint "eagle-import:R0603")
      (libsource (lib "eagle-import") (part "RESR0603"))
    )
    (comp (ref "R653")
      (value "4.02K")
      (footprint "eagle-import:R0603")
      (libsource (lib "eagle-import") (part "RESR0603"))
    )
    (comp (ref "R654")
      (value "10K")
      (footprint "eagle-import:R0603")
      (libsource (lib "eagle-import") (part "RESR0603"))
    )
    (comp (ref "RELAY1")
      (value "RELAY-SRD")
      (footprint "eagle-import:REY5-6-19.1X15.5X15.3MM")
      (libsource (lib "eagle-import") (part "RELAY-SRD"))
    )
    (comp (ref "TEST_PIN1")
      (value "POGOPIN_4")
      (footprint "eagle-import:POGOPIN_4")
      (libsource (lib "eagle-import") (part "POGOPIN_4"))
    )
    (comp (ref "U1")
      (value "BH1750")
      (footprint "eagle-import:BH1750-WSOF-6")
      (libsource (lib "eagle-import") (part "BH1750"))
    )
    (comp (ref "U2")
      (value "PCF8574DWR(UMW)")
      (footprint "eagle-import:SO-16-300MIL")
      (libsource (lib "eagle-import") (part "PCF8574T/TR"))
    )
    (comp (ref "U3")
      (value "LSM6DS3")
      (footprint "eagle-import:LGA-14L")
      (libsource (lib "eagle-import") (part "LSM6DS3"))
    )
    (comp (ref "U4")
      (value "NC/MT3608")
      (footprint "eagle-import:DBV_R-PDSO-G6")
      (libsource (lib "eagle-import") (part "MT3608"))
    )
    (comp (ref "U5")
      (value "DHT20")
      (footprint "eagle-import:CROWTAIL-DHT20-V1.0-20211013_DHT20")
      (libsource (lib "eagle-import") (part "CROWTAIL-DHT20-V1.0-20211013_DHT20"))
    )
    (comp (ref "U6")
      (value "LMV358")
      (footprint "eagle-import:SO08")
      (libsource (lib "eagle-import") (part "LMV358"))
    )
    (comp (ref "U7")
      (value "TXS0102DCUR")
      (footprint "eagle-import:VSSOP-8")
      (libsource (lib "eagle-import") (part "TXS0102DCUR"))
    )
    (comp (ref "U8")
      (value "CROWPI_POW_LCD1602")
      (footprint "eagle-import:CROWPI_POW_LCD1206")
      (libsource (lib "eagle-import") (part "CROWPI_POW_LCD1602"))
    )
    (comp (ref "U10")
      (value "MT3608")
      (footprint "eagle-import:SOT23-6L")
      (libsource (lib "eagle-import") (part "STUDY_SX1301"))
    )
    (comp (ref "U101")
      (value "BIS0001")
      (footprint "eagle-import:SOP16")
      (libsource (lib "eagle-import") (part "TM2291"))
    )
    (comp (ref "U205")
      (value "HT16K33-20P")
      (footprint "eagle-import:HT16K33-SOP20")
      (libsource (lib "eagle-import") (part "HT16K33-20P"))
    )
    (comp (ref "U215")
      (value "YY2841AS-33")
      (footprint "eagle-import:4-DIGITAL_DISPLAY")
      (libsource (lib "eagle-import") (part "4-DIGITAL_DISPLAY"))
    )
    (comp (ref "U309")
      (value "IR-3PSIP3")
      (footprint "eagle-import:VS1838B-SIP3")
      (libsource (lib "eagle-import") (part "IR-3PSIP3"))
    )
  )
  (nets
    (net (code "1") (name "/COM") (class "Default")
      (node (ref "J123") (pin "2") (pinfunction "P$2_2") (pintype "bidirectional"))
      (node (ref "RELAY1") (pin "2") (pinfunction "2_2") (pintype "bidirectional"))
    )
    (net (code "2") (name "/CS_3V") (class "Default")
      (node (ref "R24") (pin "1") (pinfunction "1_1") (pintype "passive"))
      (node (ref "U3") (pin "12") (pinfunction "CS_12") (pintype "bidirectional"))
    )
    (net (code "3") (name "/NC") (class "Default")
      (node (ref "J123") (pin "1") (pinfunction "P$1_1") (pintype "bidirectional"))
      (node (ref "RELAY1") (pin "4") (pinfunction "4_4") (pintype "bidirectional"))
    )
    (net (code "4") (name "/NO") (class "Default")
      (node (ref "J123") (pin "3") (pinfunction "P$3_3") (pintype "bidirectional"))
      (node (ref "RELAY1") (pin "5") (pinfunction "5_5") (pintype "bidirectional"))
    )
    (net (code "5") (name "/SDO") (class "Default")
      (node (ref "R25") (pin "1") (pinfunction "1_1") (pintype "passive"))
      (node (ref "U3") (pin "1") (pinfunction "SDO_1") (pintype "bidirectional"))
    )
    (net (code "6") (name "/V+") (class "Default")
      (node (ref "R276") (pin "2") (pinfunction "2_2") (pintype "passive"))
      (node (ref "RELAY1") (pin "1") (pinfunction "1_1") (pintype "bidirectional"))
    )
    (net (code "7") (name "/V-") (class "Default")
      (node (ref "D006") (pin "+") (pinfunction "+_+") (pintype "passive"))
      (node (ref "Q115") (pin "3") (pinfunction "C_3") (pintype "passive"))
      (node (ref "RELAY1") (pin "3") (pinfunction "3_3") (pintype "bidirectional"))
    )
    (net (code "8") (name "/VCC_RELAY") (class "Default")
      (node (ref "C36") (pin "2") (pinfunction "2_2") (pintype "passive"))
      (node (ref "D006") (pin "-") (pinfunction "-_-") (pintype "passive"))
      (node (ref "L11") (pin "2") (pinfunction "2_2") (pintype "bidirectional"))
      (node (ref "R276") (pin "1") (pinfunction "1_1") (pintype "passive"))
    )
    (net (code "9") (name "/~{D5_LED_R}") (class "Default")
      (node (ref "HDR1") (pin "8") (pinfunction "8_8") (pintype "bidirectional"))
      (node (ref "R5") (pin "2") (pinfunction "2_2") (pintype "passive"))
    )
    (net (code "10") (name "/~{D10_LED_Y}") (class "Default")
      (node (ref "HDR1") (pin "13") (pinfunction "13_13") (pintype "bidirectional"))
      (node (ref "R2") (pin "2") (pinfunction "2_2") (pintype "passive"))
    )
    (net (code "11") (name "/~{D11_LED_G}") (class "Default")
      (node (ref "HDR1") (pin "14") (pinfunction "14_14") (pintype "bidirectional"))
      (node (ref "R9") (pin "2") (pinfunction "2_2") (pintype "passive"))
    )
    (net (code "12") (name "1IN+") (class "Default")
      (node (ref "P102") (pin "P$1") (pinfunction "P$1_P$1") (pintype "bidirectional"))
      (node (ref "R102") (pin "1") (pinfunction "1_1") (pintype "passive"))
      (node (ref "U101") (pin "14") (pinfunction "1IN+_14") (pintype "input"))
    )
    (net (code "13") (name "1IN-") (class "Default")
      (node (ref "C105") (pin "2") (pinfunction "2_2") (pintype "passive"))
      (node (ref "P103") (pin "P$1") (pinfunction "P$1_P$1") (pintype "bidirectional"))
      (node (ref "R105") (pin "2") (pinfunction "2_2") (pintype "passive"))
      (node (ref "R106") (pin "2") (pinfunction "2_2") (pintype "passive"))
      (node (ref "U101") (pin "15") (pinfunction "1IN-_15") (pintype "input"))
    )
    (net (code "14") (name "1OUT") (class "Default")
      (node (ref "C103") (pin "2") (pinfunction "2_2") (pintype "passive"))
      (node (ref "C105") (pin "1") (pinfunction "1_1") (pintype "passive"))
      (node (ref "P100") (pin "P$1") (pinfunction "P$1_P$1") (pintype "bidirectional"))
      (node (ref "R105") (pin "1") (pinfunction "1_1") (pintype "passive"))
      (node (ref "U101") (pin "16") (pinfunction "1OUT_16") (pintype "output"))
    )
    (net (code "15") (name "2IN-") (class "Default")
      (node (ref "C104") (pin "1") (pinfunction "1_1") (pintype "passive"))
      (node (ref "P101") (pin "P$1") (pinfunction "P$1_P$1") (pintype "bidirectional"))
      (node (ref "R103") (pin "2") (pinfunction "2_2") (pintype "passive"))
      (node (ref "R104") (pin "2") (pinfunction "2_2") (pintype "passive"))
      (node (ref "U101") (pin "13") (pinfunction "2IN-_13") (pintype "input"))
    )
    (net (code "16") (name "2OUT") (class "Default")
      (node (ref "C104") (pin "2") (pinfunction "2_2") (pintype "passive"))
      (node (ref "P99") (pin "P$1") (pinfunction "P$1_P$1") (pintype "bidirectional"))
      (node (ref "R15") (pin "2") (pinfunction "3_2") (pintype "passive"))
      (node (ref "R15") (pin "3") (pinfunction "2_3") (pintype "passive"))
      (node (ref "U101") (pin "12") (pinfunction "2OUT_12") (pintype "output"))
    )
    (net (code "17") (name "A") (class "Default")
      (node (ref "P75") (pin "P$1") (pinfunction "P$1_P$1") (pintype "bidirectional"))
      (node (ref "U205") (pin "P$17") (pinfunction "P$17_P$17") (pintype "bidirectional"))
      (node (ref "U215") (pin "11") (pinfunction "11_A_11") (pintype "bidirectional"))
    )
    (net (code "18") (name "A0_ROTARY") (class "Default")
      (node (ref "C8") (pin "2") (pinfunction "2_2") (pintype "passive"))
      (node (ref "HDR2") (pin "12") (pinfunction "12_12") (pintype "bidirectional"))
      (node (ref "P1") (pin "2") (pinfunction "3_2") (pintype "passive"))
      (node (ref "P90") (pin "P$1") (pinfunction "P$1_P$1") (pintype "bidirectional"))
    )
    (net (code "19") (name "A1_SOUND") (class "Default")
      (node (ref "C27") (pin "2") (pinfunction "2_2") (pintype "passive"))
      (node (ref "C28") (pin "2") (pinfunction "2_2") (pintype "passive"))
      (node (ref "D1") (pin "2") (pinfunction "-_2") (pintype "passive"))
      (node (ref "HDR2") (pin "11") (pinfunction "11_11") (pintype "bidirectional"))
      (node (ref "R22") (pin "1") (pinfunction "1_1") (pintype "passive"))
    )
    (net (code "20") (name "A2_PIR") (class "Default")
      (node (ref "HDR2") (pin "10") (pinfunction "10_10") (pintype "bidirectional"))
      (node (ref "R112") (pin "1") (pinfunction "1_1") (pintype "passive"))
    )
    (net (code "21") (name "A3_KEY") (class "Default")
      (node (ref "HDR2") (pin "9") (pinfunction "9_9") (pintype "bidirectional"))
      (node (ref "P6") (pin "P$1") (pinfunction "P$1_P$1") (pintype "bidirectional"))
      (node (ref "R639") (pin "2") (pinfunction "2_2") (pintype "passive"))
      (node (ref "R652") (pin "2") (pinfunction "2_2") (pintype "passive"))
      (node (ref "R653") (pin "2") (pinfunction "2_2") (pintype "passive"))
      (node (ref "R654") (pin "2") (pinfunction "2_2") (pintype "passive"))
    )
    (net (code "22") (name "A4{slash}SDA") (class "Default")
      (node (ref "HDR2") (pin "8") (pinfunction "8_8") (pintype "bidirectional"))
      (node (ref "R18") (pin "2") (pinfunction "2_2") (pintype "passive"))
      (node (ref "U2") (pin "P$15") (pinfunction "SDA_P$15") (pintype "bidirectional"))
      (node (ref "U205") (pin "P$19") (pinfunction "P$19_P$19") (pintype "bidirectional"))
      (node (ref "U5") (pin "2") (pinfunction "SDA_2") (pintype "bidirectional"))
      (node (ref "U7") (pin "8") (pinfunction "B1_8") (pintype "bidirectional"))
    )
    (net (code "23") (name "A4{slash}SDA_L") (class "Default")
      (node (ref "R29") (pin "2") (pinfunction "2_2") (pintype "passive"))
      (node (ref "U1") (pin "4") (pinfunction "SDA_4") (pintype "bidirectional"))
      (node (ref "U3") (pin "14") (pinfunction "SDA_14") (pintype "bidirectional"))
      (node (ref "U7") (pin "5") (pinfunction "A1_5") (pintype "bidirectional"))
    )
    (net (code "24") (name "A5{slash}SCL") (class "Default")
      (node (ref "HDR2") (pin "7") (pinfunction "7_7") (pintype "bidirectional"))
      (node (ref "R19") (pin "2") (pinfunction "2_2") (pintype "passive"))
      (node (ref "U2") (pin "P$14") (pinfunction "SCL_P$14") (pintype "bidirectional"))
      (node (ref "U205") (pin "P$18") (pinfunction "P$18_P$18") (pintype "bidirectional"))
      (node (ref "U5") (pin "4") (pinfunction "SCL_4") (pintype "bidirectional"))
      (node (ref "U7") (pin "1") (pinfunction "B2_1") (pintype "bidirectional"))
    )
    (net (code "25") (name "A5{slash}SCL_L") (class "Default")
      (node (ref "R30") (pin "2") (pinfunction "2_2") (pintype "passive"))
      (node (ref "U1") (pin "6") (pinfunction "SCL_6") (pintype "bidirectional"))
      (node (ref "U3") (pin "13") (pinfunction "SCL_13") (pintype "bidirectional"))
      (node (ref "U7") (pin "4") (pinfunction "A2_4") (pintype "bidirectional"))
    )
    (net (code "26") (name "A6") (class "Default")
      (node (ref "HDR2") (pin "6") (pinfunction "6_6") (pintype "bidirectional"))
      (node (ref "J18") (pin "3") (pinfunction "3_3") (pintype "bidirectional"))
    )
    (net (code "27") (name "A7") (class "Default")
      (node (ref "HDR2") (pin "5") (pinfunction "5_5") (pintype "bidirectional"))
      (node (ref "J18") (pin "4") (pinfunction "4_4") (pintype "bidirectional"))
    )
    (net (code "28") (name "AREF") (class "Default")
      (node (ref "HDR2") (pin "13") (pinfunction "13_13") (pintype "bidirectional"))
    )
    (net (code "29") (name "B") (class "Default")
      (node (ref "P76") (pin "P$1") (pinfunction "P$1_P$1") (pintype "bidirectional"))
      (node (ref "U205") (pin "P$16") (pinfunction "P$16_P$16") (pintype "bidirectional"))
      (node (ref "U215") (pin "7") (pinfunction "7_B_7") (pintype "bidirectional"))
    )
    (net (code "30") (name "BOOT") (class "Default")
      (node (ref "HDR2") (pin "3") (pinfunction "3_3") (pintype "bidirectional"))
    )
    (net (code "31") (name "C") (class "Default")
      (node (ref "P77") (pin "P$1") (pinfunction "P$1_P$1") (pintype "bidirectional"))
      (node (ref "U205") (pin "P$15") (pinfunction "P$15_P$15") (pintype "bidirectional"))
      (node (ref "U215") (pin "4") (pinfunction "4_C_4") (pintype "bidirectional"))
    )
    (net (code "32") (name "D") (class "Default")
      (node (ref "P78") (pin "P$1") (pinfunction "P$1_P$1") (pintype "bidirectional"))
      (node (ref "U205") (pin "P$14") (pinfunction "P$14_P$14") (pintype "bidirectional"))
      (node (ref "U215") (pin "2") (pinfunction "2_D_2") (pintype "bidirectional"))
    )
    (net (code "33") (name "D0{slash}RX") (class "Default")
      (node (ref "HDR1") (pin "2") (pinfunction "2_2") (pintype "bidirectional"))
      (node (ref "J17") (pin "4") (pinfunction "4_4") (pintype "bidirectional"))
    )
    (net (code "34") (name "D1{slash}TX") (class "Default")
      (node (ref "HDR1") (pin "1") (pinfunction "1_1") (pintype "bidirectional"))
      (node (ref "J17") (pin "3") (pinfunction "3_3") (pintype "bidirectional"))
    )
    (net (code "35") (name "D2_IR_R") (class "Default")
      (node (ref "HDR1") (pin "5") (pinfunction "5_5") (pintype "bidirectional"))
      (node (ref "R301") (pin "2") (pinfunction "2_2") (pintype "passive"))
      (node (ref "U309") (pin "3") (pinfunction "P$3_3") (pintype "bidirectional"))
    )
    (net (code "36") (name "D3_BUZZER") (class "Default")
      (node (ref "HDR1") (pin "6") (pinfunction "6_6") (pintype "bidirectional"))
      (node (ref "R284") (pin "1") (pinfunction "1_1") (pintype "passive"))
    )
    (net (code "37") (name "D4_RELAY") (class "Default")
      (node (ref "HDR1") (pin "7") (pinfunction "7_7") (pintype "bidirectional"))
      (node (ref "R274") (pin "2") (pinfunction "2_2") (pintype "passive"))
    )
    (net (code "38") (name "D6_US_TRIG") (class "Default")
      (node (ref "HDR1") (pin "9") (pinfunction "9_9") (pintype "bidirectional"))
      (node (ref "J14") (pin "P$3") (pinfunction "3_TRIG_P$3") (pintype "bidirectional"))
      (node (ref "P37") (pin "P$1") (pinfunction "P$1_P$1") (pintype "bidirectional"))
    )
    (net (code "39") (name "D7_US_ECHO") (class "Default")
      (node (ref "HDR1") (pin "10") (pinfunction "10_10") (pintype "bidirectional"))
      (node (ref "P38") (pin "P$1") (pinfunction "P$1_P$1") (pintype "bidirectional"))
      (node (ref "R299") (pin "2") (pinfunction "2_2") (pintype "passive"))
    )
    (net (code "40") (name "D8") (class "Default")
      (node (ref "HDR1") (pin "11") (pinfunction "11_11") (pintype "bidirectional"))
    )
    (net (code "41") (name "D9_SERVO") (class "Default")
      (node (ref "HDR1") (pin "12") (pinfunction "12_12") (pintype "bidirectional"))
      (node (ref "J16") (pin "1") (pinfunction "G_1") (pintype "bidirectional"))
      (node (ref "J3") (pin "1") (pinfunction "1_1") (pintype "bidirectional"))
      (node (ref "P93") (pin "P$1") (pinfunction "P$1_P$1") (pintype "bidirectional"))
    )
    (net (code "42") (name "D12") (class "Default")
      (node (ref "HDR1") (pin "15") (pinfunction "15_15") (pintype "bidirectional"))
    )
    (net (code "43") (name "D13") (class "Default")
      (node (ref "HDR2") (pin "15") (pinfunction "15_15") (pintype "bidirectional"))
    )
    (net (code "44") (name "DB4") (class "Default")
      (node (ref "P62") (pin "P$1") (pinfunction "P$1_P$1") (pintype "bidirectional"))
      (node (ref "U2") (pin "P$9") (pinfunction "P4_P$9") (pintype "bidirectional"))
      (node (ref "U8") (pin "P$11") (pinfunction "11_D4_P$11") (pintype "bidirectional"))
    )
    (net (code "45") (name "DB5") (class "Default")
      (node (ref "P63") (pin "P$1") (pinfunction "P$1_P$1") (pintype "bidirectional"))
      (node (ref "U2") (pin "P$10") (pinfunction "P5_P$10") (pintype "bidirectional"))
      (node (ref "U8") (pin "P$12") (pinfunction "12_D5_P$12") (pintype "bidirectional"))
    )
    (net (code "46") (name "DB6") (class "Default")
      (node (ref "P64") (pin "P$1") (pinfunction "P$1_P$1") (pintype "bidirectional"))
      (node (ref "U2") (pin "P$11") (pinfunction "P6_P$11") (pintype "bidirectional"))
      (node (ref "U8") (pin "P$13") (pinfunction "13_D6_P$13") (pintype "bidirectional"))
    )
    (net (code "47") (name "DB7") (class "Default")
      (node (ref "P65") (pin "P$1") (pinfunction "P$1_P$1") (pintype "bidirectional"))
      (node (ref "U2") (pin "P$12") (pinfunction "P7_P$12") (pintype "bidirectional"))
      (node (ref "U8") (pin "P$14") (pinfunction "14_D7_P$14") (pintype "bidirectional"))
    )
    (net (code "48") (name "DIG1") (class "Default")
      (node (ref "P84") (pin "P$1") (pinfunction "P$1_P$1") (pintype "bidirectional"))
      (node (ref "U205") (pin "P$2") (pinfunction "P$2_P$2") (pintype "bidirectional"))
      (node (ref "U215") (pin "12") (pinfunction "12_COM1_12") (pintype "bidirectional"))
    )
    (net (code "49") (name "DIG2") (class "Default")
      (node (ref "P85") (pin "P$1") (pinfunction "P$1_P$1") (pintype "bidirectional"))
      (node (ref "U205") (pin "P$3") (pinfunction "P$3_P$3") (pintype "bidirectional"))
      (node (ref "U215") (pin "9") (pinfunction "9_COM2_9") (pintype "bidirectional"))
    )
    (net (code "50") (name "DIG3") (class "Default")
      (node (ref "P86") (pin "P$1") (pinfunction "P$1_P$1") (pintype "bidirectional"))
      (node (ref "U205") (pin "P$5") (pinfunction "P$5_P$5") (pintype "bidirectional"))
      (node (ref "U215") (pin "8") (pinfunction "8_COM3_8") (pintype "bidirectional"))
    )
    (net (code "51") (name "DIG4") (class "Default")
      (node (ref "P87") (pin "P$1") (pinfunction "P$1_P$1") (pintype "bidirectional"))
      (node (ref "U205") (pin "P$6") (pinfunction "P$6_P$6") (pintype "bidirectional"))
      (node (ref "U215") (pin "6") (pinfunction "6_COM4_6") (pintype "bidirectional"))
    )
    (net (code "52") (name "DP") (class "Default")
      (node (ref "P82") (pin "P$1") (pinfunction "P$1_P$1") (pintype "bidirectional"))
      (node (ref "U205") (pin "P$10") (pinfunction "P$10_P$10") (pintype "bidirectional"))
      (node (ref "U215") (pin "3") (pinfunction "3_DP_3") (pintype "bidirectional"))
    )
    (net (code "53") (name "DVI") (class "Default")
      (node (ref "C209") (pin "2") (pinfunction "2_2") (pintype "passive"))
      (node (ref "P51") (pin "P$1") (pinfunction "P$1_P$1") (pintype "bidirectional"))
      (node (ref "R271") (pin "2") (pinfunction "2_2") (pintype "passive"))
      (node (ref "U1") (pin "5") (pinfunction "DVI_5") (pintype "bidirectional"))
    )
    (net (code "54") (name "E") (class "Default")
      (node (ref "P79") (pin "P$1") (pinfunction "P$1_P$1") (pintype "bidirectional"))
      (node (ref "U205") (pin "P$13") (pinfunction "P$13_P$13") (pintype "bidirectional"))
      (node (ref "U215") (pin "1") (pinfunction "1_E_1") (pintype "bidirectional"))
    )
    (net (code "55") (name "E_LCD") (class "Default")
      (node (ref "P60") (pin "P$1") (pinfunction "P$1_P$1") (pintype "bidirectional"))
      (node (ref "U2") (pin "P$6") (pinfunction "P2_P$6") (pintype "bidirectional"))
      (node (ref "U8") (pin "P$6") (pinfunction "6_E_P$6") (pintype "bidirectional"))
    )
    (net (code "56") (name "F") (class "Default")
      (node (ref "P80") (pin "P$1") (pinfunction "P$1_P$1") (pintype "bidirectional"))
      (node (ref "U205") (pin "P$12") (pinfunction "P$12_P$12") (pintype "bidirectional"))
      (node (ref "U215") (pin "10") (pinfunction "10_F_10") (pintype "bidirectional"))
    )
    (net (code "57") (name "FB") (class "Default")
      (node (ref "C47") (pin "2") (pinfunction "2_2") (pintype "passive"))
      (node (ref "P4") (pin "P$1") (pinfunction "P$1_P$1") (pintype "bidirectional"))
      (node (ref "R75") (pin "1") (pinfunction "1_1") (pintype "passive"))
      (node (ref "R76") (pin "2") (pinfunction "2_2") (pintype "passive"))
      (node (ref "U10") (pin "3") (pinfunction "FB_3") (pintype "bidirectional"))
    )
    (net (code "58") (name "G") (class "Default")
      (node (ref "P81") (pin "P$1") (pinfunction "P$1_P$1") (pintype "bidirectional"))
      (node (ref "U205") (pin "P$11") (pinfunction "P$11_P$11") (pintype "bidirectional"))
      (node (ref "U215") (pin "5") (pinfunction "5_G_5") (pintype "bidirectional"))
    )
    (net (code "59") (name "GND") (class "Default")
      (node (ref "C101") (pin "1") (pinfunction "1_1") (pintype "passive"))
      (node (ref "C102") (pin "1") (pinfunction "1_1") (pintype "passive"))
      (node (ref "C107") (pin "2") (pinfunction "2_2") (pintype "passive"))
      (node (ref "C108") (pin "2") (pinfunction "2_2") (pintype "passive"))
      (node (ref "C14") (pin "1") (pinfunction "1_1") (pintype "passive"))
      (node (ref "C16") (pin "1") (pinfunction "1_1") (pintype "passive"))
      (node (ref "C17") (pin "2") (pinfunction "2_2") (pintype "passive"))
      (node (ref "C18") (pin "1") (pinfunction "1_1") (pintype "passive"))
      (node (ref "C19") (pin "2") (pinfunction "2_2") (pintype "passive"))
      (node (ref "C209") (pin "1") (pinfunction "1_1") (pintype "passive"))
      (node (ref "C214") (pin "1") (pinfunction "1_1") (pintype "passive"))
      (node (ref "C225") (pin "1") (pinfunction "1_1") (pintype "passive"))
      (node (ref "C25") (pin "1") (pinfunction "1_1") (pintype "passive"))
      (node (ref "C27") (pin "1") (pinfunction "1_1") (pintype "passive"))
      (node (ref "C28") (pin "1") (pinfunction "1_1") (pintype "passive"))
      (node (ref "C29") (pin "1") (pinfunction "1_1") (pintype "passive"))
      (node (ref "C31") (pin "-") (pinfunction "-_-") (pintype "passive"))
      (node (ref "C35") (pin "1") (pinfunction "1_1") (pintype "passive"))
      (node (ref "C36") (pin "1") (pinfunction "1_1") (pintype "passive"))
      (node (ref "C37") (pin "1") (pinfunction "1_1") (pintype "passive"))
      (node (ref "C48") (pin "1") (pinfunction "1_1") (pintype "passive"))
      (node (ref "C51") (pin "1") (pinfunction "1_1") (pintype "passive"))
      (node (ref "C53") (pin "1") (pinfunction "1_1") (pintype "passive"))
      (node (ref "C55") (pin "1") (pinfunction "1_1") (pintype "passive"))
      (node (ref "C56") (pin "1") (pinfunction "1_1") (pintype "passive"))
      (node (ref "C58") (pin "1") (pinfunction "1_1") (pintype "passive"))
      (node (ref "C59") (pin "1") (pinfunction "1_1") (pintype "passive"))
      (node (ref "C6") (pin "1") (pinfunction "1_1") (pintype "passive"))
      (node (ref "C60") (pin "1") (pinfunction "1_1") (pintype "passive"))
      (node (ref "C7") (pin "1") (pinfunction "1_1") (pintype "passive"))
      (node (ref "C8") (pin "1") (pinfunction "1_1") (pintype "passive"))
      (node (ref "HDR1") (pin "4") (pinfunction "4_4") (pintype "bidirectional"))
      (node (ref "HDR2") (pin "2") (pinfunction "2_2") (pintype "bidirectional"))
      (node (ref "J101") (pin "3") (pinfunction "G_3") (pintype "bidirectional"))
      (node (ref "J14") (pin "P$1") (pinfunction "1_GND_P$1") (pintype "bidirectional"))
      (node (ref "J16") (pin "3") (pinfunction "S_3") (pintype "bidirectional"))
      (node (ref "J17") (pin "1") (pinfunction "1_1") (pintype "bidirectional"))
      (node (ref "J18") (pin "1") (pinfunction "1_1") (pintype "bidirectional"))
      (node (ref "J19") (pin "2") (pinfunction "-_2") (pintype "bidirectional"))
      (node (ref "J23") (pin "1") (pinfunction "1_1") (pintype "passive"))
      (node (ref "J24") (pin "1") (pinfunction "1_1") (pintype "passive"))
      (node (ref "J3") (pin "4") (pinfunction "4_4") (pintype "bidirectional"))
      (node (ref "J3") (pin "SS1") (pinfunction "SS1_SS1") (pintype "bidirectional"))
      (node (ref "J3") (pin "SS2") (pinfunction "SS2_SS2") (pintype "bidirectional"))
      (node (ref "J7") (pin "1") (pinfunction "1_1") (pintype "bidirectional"))
      (node (ref "J8") (pin "4") (pinfunction "4_4") (pintype "bidirectional"))
      (node (ref "J8") (pin "5") (pinfunction "SS1_5") (pintype "bidirectional"))
      (node (ref "J8") (pin "6") (pinfunction "SS2_6") (pintype "bidirectional"))
      (node (ref "K1") (pin "P$1") (pinfunction "P$1_P$1") (pintype "bidirectional"))
      (node (ref "K2") (pin "P$1") (pinfunction "P$1_P$1") (pintype "bidirectional"))
      (node (ref "K3") (pin "P$1") (pinfunction "P$1_P$1") (pintype "bidirectional"))
      (node (ref "P1") (pin "1") (pinfunction "1_1") (pintype "passive"))
      (node (ref "P39") (pin "P$1") (pinfunction "P$1_P$1") (pintype "bidirectional"))
      (node (ref "P43") (pin "P$1") (pinfunction "P$1_P$1") (pintype "bidirectional"))
      (node (ref "P50") (pin "P$1") (pinfunction "P$1_P$1") (pintype "bidirectional"))
      (node (ref "P52") (pin "P$1") (pinfunction "P$1_P$1") (pintype "bidirectional"))
      (node (ref "P56") (pin "P$1") (pinfunction "P$1_P$1") (pintype "bidirectional"))
      (node (ref "P57") (pin "P$1") (pinfunction "P$1_P$1") (pintype "bidirectional"))
      (node (ref "P74") (pin "P$1") (pinfunction "P$1_P$1") (pintype "bidirectional"))
      (node (ref "P88") (pin "P$1") (pinfunction "P$1_P$1") (pintype "bidirectional"))
      (node (ref "P91") (pin "P$1") (pinfunction "P$1_P$1") (pintype "bidirectional"))
      (node (ref "P94") (pin "P$1") (pinfunction "P$1_P$1") (pintype "bidirectional"))
      (node (ref "Q1") (pin "2") (pinfunction "E_2") (pintype "passive"))
      (node (ref "Q103") (pin "2") (pinfunction "E_2") (pintype "passive"))
      (node (ref "Q108") (pin "2") (pinfunction "E_2") (pintype "passive"))
      (node (ref "Q115") (pin "2") (pinfunction "E_2") (pintype "passive"))
      (node (ref "Q2") (pin "2") (pinfunction "E_2") (pintype "passive"))
      (node (ref "Q3") (pin "2") (pinfunction "E_2") (pintype "passive"))
      (node (ref "R1") (pin "1") (pinfunction "1_1") (pintype "passive"))
      (node (ref "R10") (pin "2") (pinfunction "2_2") (pintype "passive"))
      (node (ref "R101") (pin "1") (pinfunction "1_1") (pintype "passive"))
      (node (ref "R108") (pin "1") (pinfunction "1_1") (pintype "passive"))
      (node (ref "R14") (pin "1") (pinfunction "1_1") (pintype "passive"))
      (node (ref "R20") (pin "1") (pinfunction "1_1") (pintype "passive"))
      (node (ref "R21") (pin "1") (pinfunction "1_1") (pintype "passive"))
      (node (ref "R22") (pin "2") (pinfunction "2_2") (pintype "passive"))
      (node (ref "R238") (pin "1") (pinfunction "1_1") (pintype "passive"))
      (node (ref "R26") (pin "1") (pinfunction "1_1") (pintype "passive"))
      (node (ref "R268") (pin "1") (pinfunction "1_1") (pintype "passive"))
      (node (ref "R27") (pin "1") (pinfunction "1_1") (pintype "passive"))
      (node (ref "R273") (pin "1") (pinfunction "1_1") (pintype "passive"))
      (node (ref "R302") (pin "1") (pinfunction "1_1") (pintype "passive"))
      (node (ref "R307") (pin "2") (pinfunction "2_2") (pintype "passive"))
      (node (ref "R324") (pin "2") (pinfunction "2_2") (pintype "passive"))
      (node (ref "R4") (pin "1") (pinfunction "1_1") (pintype "passive"))
      (node (ref "R6") (pin "1") (pinfunction "1_1") (pintype "passive"))
      (node (ref "R76") (pin "1") (pinfunction "1_1") (pintype "passive"))
      (node (ref "TEST_PIN1") (pin "1") (pinfunction "1_1") (pintype "bidirectional"))
      (node (ref "U1") (pin "3") (pinfunction "GND\\_3") (pintype "bidirectional"))
      (node (ref "U10") (pin "2") (pinfunction "GND_2") (pintype "bidirectional"))
      (node (ref "U101") (pin "7") (pinfunction "VSS_7") (pintype "power_in"))
      (node (ref "U2") (pin "P$8") (pinfunction "VSS_P$8") (pintype "bidirectional"))
      (node (ref "U205") (pin "P$1") (pinfunction "P$1_P$1") (pintype "bidirectional"))
      (node (ref "U3") (pin "6") (pinfunction "GND_6") (pintype "power_in"))
      (node (ref "U3") (pin "7") (pinfunction "GND_7") (pintype "power_in"))
      (node (ref "U309") (pin "2") (pinfunction "P$2_2") (pintype "bidirectional"))
      (node (ref "U4") (pin "2") (pinfunction "GND_2") (pintype "bidirectional"))
      (node (ref "U5") (pin "3") (pinfunction "GND_3") (pintype "bidirectional"))
      (node (ref "U6") (pin "4") (pinfunction "GND_4") (pintype "power_in"))
      (node (ref "U7") (pin "2") (pinfunction "GND_2") (pintype "bidirectional"))
      (node (ref "U8") (pin "P$1") (pinfunction "1_VSS_P$1") (pintype "bidirectional"))
    )
    (net (code "60") (name "IB") (class "Default")
      (node (ref "P98") (pin "P$1") (pinfunction "P$1_P$1") (pintype "bidirectional"))
      (node (ref "R108") (pin "2") (pinfunction "2_2") (pintype "passive"))
      (node (ref "U101") (pin "10") (pinfunction "IB_10") (pintype "bidirectional"))
    )
    (net (code "61") (name "LED_G") (class "Default")
      (node (ref "P30") (pin "P$1") (pinfunction "P$1_P$1") (pintype "bidirectional"))
      (node (ref "Q3") (pin "1") (pinfunction "B_1") (pintype "passive"))
      (node (ref "R6") (pin "2") (pinfunction "2_2") (pintype "passive"))
      (node (ref "R9") (pin "1") (pinfunction "1_1") (pintype "passive"))
    )
    (net (code "62") (name "LED_R") (class "Default")
      (node (ref "P42") (pin "P$1") (pinfunction "P$1_P$1") (pintype "bidirectional"))
      (node (ref "Q1") (pin "1") (pinfunction "B_1") (pintype "passive"))
      (node (ref "R4") (pin "2") (pinfunction "2_2") (pintype "passive"))
      (node (ref "R5") (pin "1") (pinfunction "1_1") (pintype "passive"))
    )
    (net (code "63") (name "LED_Y") (class "Default")
      (node (ref "P7") (pin "P$1") (pinfunction "P$1_P$1") (pintype "bidirectional"))
      (node (ref "Q2") (pin "1") (pinfunction "B_1") (pintype "passive"))
      (node (ref "R1") (pin "2") (pinfunction "2_2") (pintype "passive"))
      (node (ref "R2") (pin "1") (pinfunction "1_1") (pintype "passive"))
    )
    (net (code "64") (name "LIGHT") (class "Default")
      (node (ref "P61") (pin "P$1") (pinfunction "P$1_P$1") (pintype "bidirectional"))
      (node (ref "R321") (pin "2") (pinfunction "2_2") (pintype "passive"))
      (node (ref "U2") (pin "P$7") (pinfunction "P3_P$7") (pintype "bidirectional"))
    )
    (net (code "65") (name "NANO_R4_RST") (class "Default")
      (node (ref "HDR1") (pin "3") (pinfunction "3_3") (pintype "bidirectional"))
    )
    (net (code "66") (name "Net-(BUZ1-1+)") (class "Default")
      (node (ref "BUZ1") (pin "1") (pinfunction "1+_1") (pintype "bidirectional"))
      (node (ref "D004") (pin "-") (pinfunction "-_-") (pintype "passive"))
      (node (ref "R303") (pin "2") (pinfunction "2_2") (pintype "passive"))
    )
    (net (code "67") (name "Net-(BUZ1-2-)") (class "Default")
      (node (ref "BUZ1") (pin "2") (pinfunction "2-_2") (pintype "bidirectional"))
      (node (ref "D004") (pin "+") (pinfunction "+_+") (pintype "passive"))
      (node (ref "Q103") (pin "3") (pinfunction "C_3") (pintype "passive"))
    )
    (net (code "68") (name "Net-(C103-Pad1)") (class "Default")
      (node (ref "C103") (pin "1") (pinfunction "1_1") (pintype "passive"))
      (node (ref "R103") (pin "1") (pinfunction "1_1") (pintype "passive"))
    )
    (net (code "69") (name "Net-(C225-Pad2)") (class "Default")
      (node (ref "C225") (pin "2") (pinfunction "2_2") (pintype "passive"))
      (node (ref "R106") (pin "1") (pinfunction "1_1") (pintype "passive"))
    )
    (net (code "70") (name "Net-(D1-+)") (class "Default")
      (node (ref "D1") (pin "1") (pinfunction "+_1") (pintype "passive"))
      (node (ref "U6") (pin "1") (pinfunction "OUT1_1") (pintype "output"))
      (node (ref "U6") (pin "2") (pinfunction "-IN1_2") (pintype "input"))
    )
    (net (code "71") (name "Net-(D002-A)") (class "Default")
      (node (ref "D002") (pin "1") (pinfunction "A_1") (pintype "passive"))
      (node (ref "R3") (pin "2") (pinfunction "2_2") (pintype "passive"))
    )
    (net (code "72") (name "Net-(D002-C)") (class "Default")
      (node (ref "D002") (pin "2") (pinfunction "C_2") (pintype "passive"))
      (node (ref "Q2") (pin "3") (pinfunction "C_3") (pintype "passive"))
    )
    (net (code "73") (name "Net-(D005-A)") (class "Default")
      (node (ref "D005") (pin "1") (pinfunction "A_1") (pintype "passive"))
      (node (ref "R11") (pin "2") (pinfunction "2_2") (pintype "passive"))
    )
    (net (code "74") (name "Net-(D005-C)") (class "Default")
      (node (ref "D005") (pin "2") (pinfunction "C_2") (pintype "passive"))
      (node (ref "Q3") (pin "3") (pinfunction "C_3") (pintype "passive"))
    )
    (net (code "75") (name "Net-(D11-A)") (class "Default")
      (node (ref "D11") (pin "1") (pinfunction "A_1") (pintype "passive"))
      (node (ref "R7") (pin "2") (pinfunction "2_2") (pintype "passive"))
    )
    (net (code "76") (name "Net-(D11-C)") (class "Default")
      (node (ref "D11") (pin "2") (pinfunction "C_2") (pintype "passive"))
      (node (ref "Q1") (pin "3") (pinfunction "C_3") (pintype "passive"))
    )
    (net (code "77") (name "Net-(HDR2-Pad1)") (class "Default")
      (node (ref "HDR2") (pin "1") (pinfunction "1_1") (pintype "bidirectional"))
      (node (ref "R13") (pin "1") (pinfunction "1_1") (pintype "passive"))
    )
    (net (code "78") (name "Net-(J14-2_ECHO)") (class "Default")
      (node (ref "J14") (pin "P$2") (pinfunction "2_ECHO_P$2") (pintype "bidirectional"))
      (node (ref "R299") (pin "1") (pinfunction "1_1") (pintype "passive"))
    )
    (net (code "79") (name "Net-(J19-+)") (class "Default")
      (node (ref "C26") (pin "1") (pinfunction "1_1") (pintype "passive"))
      (node (ref "J19") (pin "1") (pinfunction "+_1") (pintype "bidirectional"))
      (node (ref "R16") (pin "1") (pinfunction "1_1") (pintype "passive"))
    )
    (net (code "80") (name "Net-(K1-PadP$2)") (class "Default")
      (node (ref "K1") (pin "P$2") (pinfunction "P$2_P$2") (pintype "bidirectional"))
      (node (ref "R652") (pin "1") (pinfunction "1_1") (pintype "passive"))
    )
    (net (code "81") (name "Net-(K2-PadP$2)") (class "Default")
      (node (ref "K2") (pin "P$2") (pinfunction "P$2_P$2") (pintype "bidirectional"))
      (node (ref "R653") (pin "1") (pinfunction "1_1") (pintype "passive"))
    )
    (net (code "82") (name "Net-(K3-PadP$2)") (class "Default")
      (node (ref "K3") (pin "P$2") (pinfunction "P$2_P$2") (pintype "bidirectional"))
      (node (ref "R654") (pin "1") (pinfunction "1_1") (pintype "passive"))
    )
    (net (code "83") (name "Net-(Q103-B)") (class "Default")
      (node (ref "Q103") (pin "1") (pinfunction "B_1") (pintype "passive"))
      (node (ref "R284") (pin "2") (pinfunction "2_2") (pintype "passive"))
      (node (ref "R302") (pin "2") (pinfunction "2_2") (pintype "passive"))
    )
    (net (code "84") (name "Net-(Q108-B)") (class "Default")
      (node (ref "Q108") (pin "1") (pinfunction "B_1") (pintype "passive"))
      (node (ref "R321") (pin "1") (pinfunction "1_1") (pintype "passive"))
      (node (ref "R324") (pin "1") (pinfunction "1_1") (pintype "passive"))
    )
    (net (code "85") (name "Net-(Q108-C)") (class "Default")
      (node (ref "Q108") (pin "3") (pinfunction "C_3") (pintype "passive"))
      (node (ref "U8") (pin "P$16") (pinfunction "16_LED_K_P$16") (pintype "bidirectional"))
    )
    (net (code "86") (name "Net-(Q115-B)") (class "Default")
      (node (ref "Q115") (pin "1") (pinfunction "B_1") (pintype "passive"))
      (node (ref "R273") (pin "2") (pinfunction "2_2") (pintype "passive"))
      (node (ref "R274") (pin "1") (pinfunction "1_1") (pintype "passive"))
    )
    (net (code "87") (name "Net-(R23-3)") (class "Default")
      (node (ref "R21") (pin "2") (pinfunction "2_2") (pintype "passive"))
      (node (ref "R23") (pin "2") (pinfunction "3_2") (pintype "passive"))
      (node (ref "U6") (pin "6") (pinfunction "-IN2_6") (pintype "input"))
    )
    (net (code "88") (name "Net-(R31-Pad1)") (class "Default")
      (node (ref "R31") (pin "1") (pinfunction "1_1") (pintype "passive"))
      (node (ref "TEST_PIN1") (pin "2") (pinfunction "2_2") (pintype "bidirectional"))
    )
    (net (code "89") (name "Net-(R104-Pad1)") (class "Default")
      (node (ref "R104") (pin "1") (pinfunction "1_1") (pintype "passive"))
      (node (ref "R15") (pin "1") (pinfunction "1_1") (pintype "passive"))
    )
    (net (code "90") (name "Net-(R268-3)") (class "Default")
      (node (ref "R268") (pin "2") (pinfunction "3_2") (pintype "passive"))
      (node (ref "U8") (pin "P$3") (pinfunction "3_V0_P$3") (pintype "bidirectional"))
    )
    (net (code "91") (name "Net-(U1-ADDR)") (class "Default")
      (node (ref "R237") (pin "1") (pinfunction "1_1") (pintype "passive"))
      (node (ref "R238") (pin "2") (pinfunction "2_2") (pintype "passive"))
      (node (ref "U1") (pin "2") (pinfunction "ADDR_2") (pintype "bidirectional"))
    )
    (net (code "92") (name "Net-(U2-A0)") (class "Default")
      (node (ref "R17") (pin "2") (pinfunction "2_2") (pintype "passive"))
      (node (ref "U2") (pin "P$1") (pinfunction "A0_P$1") (pintype "bidirectional"))
    )
    (net (code "93") (name "Net-(U2-A1)") (class "Default")
      (node (ref "R87") (pin "2") (pinfunction "2_2") (pintype "passive"))
      (node (ref "U2") (pin "P$2") (pinfunction "A1_P$2") (pintype "bidirectional"))
    )
    (net (code "94") (name "Net-(U2-A2)") (class "Default")
      (node (ref "R89") (pin "2") (pinfunction "2_2") (pintype "passive"))
      (node (ref "U2") (pin "P$3") (pinfunction "A2_P$3") (pintype "bidirectional"))
    )
    (net (code "95") (name "Net-(U3-SCX)") (class "Default")
      (node (ref "R27") (pin "2") (pinfunction "2_2") (pintype "passive"))
      (node (ref "U3") (pin "3") (pinfunction "SCX_3") (pintype "bidirectional"))
    )
    (net (code "96") (name "Net-(U3-SDX)") (class "Default")
      (node (ref "R26") (pin "2") (pinfunction "2_2") (pintype "passive"))
      (node (ref "U3") (pin "2") (pinfunction "SDX_2") (pintype "bidirectional"))
    )
    (net (code "97") (name "Net-(U4-FB)") (class "Default")
      (node (ref "R10") (pin "1") (pinfunction "1_1") (pintype "passive"))
      (node (ref "R8") (pin "2") (pinfunction "2_2") (pintype "passive"))
      (node (ref "U4") (pin "3") (pinfunction "FB_3") (pintype "bidirectional"))
    )
    (net (code "98") (name "Net-(U4-SW)") (class "Default")
      (node (ref "D008") (pin "A") (pinfunction "A_A") (pintype "passive"))
      (node (ref "L3") (pin "2") (pinfunction "2_2") (pintype "passive"))
      (node (ref "U4") (pin "1") (pinfunction "SW_1") (pintype "bidirectional"))
    )
    (net (code "99") (name "Net-(U6A-+IN1)") (class "Default")
      (node (ref "R23") (pin "1") (pinfunction "1_1") (pintype "passive"))
      (node (ref "U6") (pin "3") (pinfunction "+IN1_3") (pintype "input"))
      (node (ref "U6") (pin "7") (pinfunction "OUT2_7") (pintype "output"))
    )
    (net (code "100") (name "Net-(U6B-+IN2)") (class "Default")
      (node (ref "C26") (pin "2") (pinfunction "2_2") (pintype "passive"))
      (node (ref "R20") (pin "2") (pinfunction "2_2") (pintype "passive"))
      (node (ref "U6") (pin "5") (pinfunction "+IN2_5") (pintype "input"))
    )
    (net (code "101") (name "Net-(U7-OE)") (class "Default")
      (node (ref "R12") (pin "2") (pinfunction "2_2") (pintype "passive"))
      (node (ref "R14") (pin "2") (pinfunction "2_2") (pintype "passive"))
      (node (ref "U7") (pin "6") (pinfunction "OE_6") (pintype "bidirectional"))
    )
    (net (code "102") (name "Net-(U10-EN)") (class "Default")
      (node (ref "R28") (pin "2") (pinfunction "2_2") (pintype "passive"))
      (node (ref "U10") (pin "4") (pinfunction "EN_4") (pintype "bidirectional"))
    )
    (net (code "103") (name "Net-(U10-LX)") (class "Default")
      (node (ref "D10") (pin "+") (pinfunction "+_+") (pintype "passive"))
      (node (ref "L8") (pin "2") (pinfunction "2_2") (pintype "passive"))
      (node (ref "U10") (pin "1") (pinfunction "LX_1") (pintype "bidirectional"))
    )
    (net (code "104") (name "Net-(U101-A)") (class "Default")
      (node (ref "R113") (pin "2") (pinfunction "2_2") (pintype "passive"))
      (node (ref "U101") (pin "1") (pinfunction "A_1") (pintype "bidirectional"))
    )
    (net (code "105") (name "Net-(U101-RR1)") (class "Default")
      (node (ref "R111") (pin "1") (pinfunction "1_1") (pintype "passive"))
      (node (ref "U101") (pin "3") (pinfunction "RR1_3") (pintype "bidirectional"))
    )
    (net (code "106") (name "Net-(U101-RR2)") (class "Default")
      (node (ref "R110") (pin "2") (pinfunction "2_2") (pintype "passive"))
      (node (ref "U101") (pin "6") (pinfunction "RR2_6") (pintype "bidirectional"))
    )
    (net (code "107") (name "Net-(U101-VC)") (class "Default")
      (node (ref "R109") (pin "2") (pinfunction "2_2") (pintype "passive"))
      (node (ref "U101") (pin "9") (pinfunction "VC_9") (pintype "bidirectional"))
    )
    (net (code "108") (name "PIR") (class "Default")
      (node (ref "P96") (pin "P$1") (pinfunction "P$1_P$1") (pintype "bidirectional"))
      (node (ref "R112") (pin "2") (pinfunction "2_2") (pintype "passive"))
      (node (ref "U101") (pin "2") (pinfunction "VO_2") (pintype "bidirectional"))
    )
    (net (code "109") (name "RC1") (class "Default")
      (node (ref "C108") (pin "1") (pinfunction "1_1") (pintype "passive"))
      (node (ref "P104") (pin "P$1") (pinfunction "P$1_P$1") (pintype "bidirectional"))
      (node (ref "R111") (pin "2") (pinfunction "2_2") (pintype "passive"))
      (node (ref "U101") (pin "4") (pinfunction "RC1_4") (pintype "bidirectional"))
    )
    (net (code "110") (name "RC2") (class "Default")
      (node (ref "C107") (pin "1") (pinfunction "1_1") (pintype "passive"))
      (node (ref "P105") (pin "P$1") (pinfunction "P$1_P$1") (pintype "bidirectional"))
      (node (ref "R110") (pin "1") (pinfunction "1_1") (pintype "passive"))
      (node (ref "U101") (pin "5") (pinfunction "RC2_5") (pintype "bidirectional"))
    )
    (net (code "111") (name "RED") (class "Default")
      (node (ref "D130") (pin "2") (pinfunction "2_K_2") (pintype "passive"))
      (node (ref "P5") (pin "P$1") (pinfunction "P$1_P$1") (pintype "bidirectional"))
      (node (ref "R307") (pin "1") (pinfunction "1_1") (pintype "passive"))
    )
    (net (code "112") (name "RS") (class "Default")
      (node (ref "P58") (pin "P$1") (pinfunction "P$1_P$1") (pintype "bidirectional"))
      (node (ref "U2") (pin "P$4") (pinfunction "P0_P$4") (pintype "bidirectional"))
      (node (ref "U8") (pin "P$4") (pinfunction "4_RS_P$4") (pintype "bidirectional"))
    )
    (net (code "113") (name "RW") (class "Default")
      (node (ref "P59") (pin "P$1") (pinfunction "P$1_P$1") (pintype "bidirectional"))
      (node (ref "U2") (pin "P$5") (pinfunction "P1_P$5") (pintype "bidirectional"))
      (node (ref "U8") (pin "P$5") (pinfunction "5_RW_P$5") (pintype "bidirectional"))
    )
    (net (code "114") (name "S") (class "Default")
      (node (ref "C101") (pin "2") (pinfunction "2_2") (pintype "passive"))
      (node (ref "J101") (pin "2") (pinfunction "S_2") (pintype "bidirectional"))
      (node (ref "P95") (pin "P$1") (pinfunction "P$1_P$1") (pintype "bidirectional"))
      (node (ref "R101") (pin "2") (pinfunction "2_2") (pintype "passive"))
      (node (ref "R102") (pin "2") (pinfunction "2_2") (pintype "passive"))
    )
    (net (code "115") (name "SEN_3V3") (class "Default")
      (node (ref "C14") (pin "2") (pinfunction "2_2") (pintype "passive"))
      (node (ref "C17") (pin "1") (pinfunction "1_1") (pintype "passive"))
      (node (ref "C29") (pin "2") (pinfunction "2_2") (pintype "passive"))
      (node (ref "HDR2") (pin "14") (pinfunction "14_14") (pintype "bidirectional"))
      (node (ref "P49") (pin "P$1") (pinfunction "P$1_P$1") (pintype "bidirectional"))
      (node (ref "R12") (pin "1") (pinfunction "1_1") (pintype "passive"))
      (node (ref "R237") (pin "2") (pinfunction "2_2") (pintype "passive"))
      (node (ref "R24") (pin "2") (pinfunction "2_2") (pintype "passive"))
      (node (ref "R25") (pin "2") (pinfunction "2_2") (pintype "passive"))
      (node (ref "R271") (pin "1") (pinfunction "1_1") (pintype "passive"))
      (node (ref "R29") (pin "1") (pinfunction "1_1") (pintype "passive"))
      (node (ref "R30") (pin "1") (pinfunction "1_1") (pintype "passive"))
      (node (ref "U1") (pin "1") (pinfunction "VCC_1") (pintype "bidirectional"))
      (node (ref "U3") (pin "5") (pinfunction "VDDIO_5") (pintype "power_in"))
      (node (ref "U3") (pin "8") (pinfunction "VDD_8") (pintype "power_in"))
      (node (ref "U7") (pin "3") (pinfunction "VCCA_3") (pintype "bidirectional"))
    )
    (net (code "116") (name "USB_D_N") (class "Default")
      (node (ref "J6") (pin "1") (pinfunction "1_1") (pintype "bidirectional"))
      (node (ref "J8") (pin "3") (pinfunction "3_3") (pintype "bidirectional"))
      (node (ref "TEST_PIN1") (pin "4") (pinfunction "4_4") (pintype "bidirectional"))
    )
    (net (code "117") (name "USB_D_P") (class "Default")
      (node (ref "J5") (pin "1") (pinfunction "1_1") (pintype "bidirectional"))
      (node (ref "J8") (pin "2") (pinfunction "2_2") (pintype "bidirectional"))
      (node (ref "TEST_PIN1") (pin "3") (pinfunction "3_3") (pintype "bidirectional"))
    )
    (net (code "118") (name "VCC_5V") (class "Default")
      (node (ref "C102") (pin "2") (pinfunction "2_2") (pintype "passive"))
      (node (ref "C16") (pin "2") (pinfunction "2_2") (pintype "passive"))
      (node (ref "C18") (pin "2") (pinfunction "2_2") (pintype "passive"))
      (node (ref "C19") (pin "1") (pinfunction "1_1") (pintype "passive"))
      (node (ref "C214") (pin "2") (pinfunction "2_2") (pintype "passive"))
      (node (ref "C25") (pin "2") (pinfunction "2_2") (pintype "passive"))
      (node (ref "C35") (pin "2") (pinfunction "2_2") (pintype "passive"))
      (node (ref "C37") (pin "2") (pinfunction "2_2") (pintype "passive"))
      (node (ref "C47") (pin "1") (pinfunction "1_1") (pintype "passive"))
      (node (ref "C48") (pin "2") (pinfunction "2_2") (pintype "passive"))
      (node (ref "C6") (pin "2") (pinfunction "2_2") (pintype "passive"))
      (node (ref "C7") (pin "2") (pinfunction "2_2") (pintype "passive"))
      (node (ref "D10") (pin "-") (pinfunction "-_-") (pintype "passive"))
      (node (ref "D130") (pin "1") (pinfunction "1_A_1") (pintype "passive"))
      (node (ref "HDR2") (pin "4") (pinfunction "4_4") (pintype "bidirectional"))
      (node (ref "J101") (pin "1") (pinfunction "D_1") (pintype "bidirectional"))
      (node (ref "J14") (pin "P$4") (pinfunction "4VCC_P$4") (pintype "bidirectional"))
      (node (ref "J17") (pin "2") (pinfunction "2_2") (pintype "bidirectional"))
      (node (ref "J18") (pin "2") (pinfunction "2_2") (pintype "bidirectional"))
      (node (ref "L11") (pin "1") (pinfunction "1_1") (pintype "bidirectional"))
      (node (ref "P1") (pin "3") (pinfunction "2_3") (pintype "passive"))
      (node (ref "P3") (pin "P$1") (pinfunction "P$1_P$1") (pintype "bidirectional"))
      (node (ref "P36") (pin "P$1") (pinfunction "P$1_P$1") (pintype "bidirectional"))
      (node (ref "P40") (pin "P$1") (pinfunction "P$1_P$1") (pintype "bidirectional"))
      (node (ref "P48") (pin "P$1") (pinfunction "P$1_P$1") (pintype "bidirectional"))
      (node (ref "P54") (pin "P$1") (pinfunction "P$1_P$1") (pintype "bidirectional"))
      (node (ref "P55") (pin "P$1") (pinfunction "P$1_P$1") (pintype "bidirectional"))
      (node (ref "P73") (pin "P$1") (pinfunction "P$1_P$1") (pintype "bidirectional"))
      (node (ref "P83") (pin "P$1") (pinfunction "P$1_P$1") (pintype "bidirectional"))
      (node (ref "P89") (pin "P$1") (pinfunction "P$1_P$1") (pintype "bidirectional"))
      (node (ref "P97") (pin "P$1") (pinfunction "P$1_P$1") (pintype "bidirectional"))
      (node (ref "R109") (pin "1") (pinfunction "1_1") (pintype "passive"))
      (node (ref "R11") (pin "1") (pinfunction "1_1") (pintype "passive"))
      (node (ref "R113") (pin "1") (pinfunction "1_1") (pintype "passive"))
      (node (ref "R16") (pin "2") (pinfunction "2_2") (pintype "passive"))
      (node (ref "R17") (pin "1") (pinfunction "1_1") (pintype "passive"))
      (node (ref "R18") (pin "1") (pinfunction "1_1") (pintype "passive"))
      (node (ref "R19") (pin "1") (pinfunction "1_1") (pintype "passive"))
      (node (ref "R268") (pin "3") (pinfunction "2_3") (pintype "passive"))
      (node (ref "R3") (pin "1") (pinfunction "1_1") (pintype "passive"))
      (node (ref "R301") (pin "1") (pinfunction "1_1") (pintype "passive"))
      (node (ref "R303") (pin "1") (pinfunction "1_1") (pintype "passive"))
      (node (ref "R639") (pin "1") (pinfunction "1_1") (pintype "passive"))
      (node (ref "R7") (pin "1") (pinfunction "1_1") (pintype "passive"))
      (node (ref "R75") (pin "2") (pinfunction "2_2") (pintype "passive"))
      (node (ref "R87") (pin "1") (pinfunction "1_1") (pintype "passive"))
      (node (ref "R89") (pin "1") (pinfunction "1_1") (pintype "passive"))
      (node (ref "U101") (pin "11") (pinfunction "VDD_11") (pintype "power_in"))
      (node (ref "U101") (pin "8") (pinfunction "~{RESET}_8") (pintype "input"))
      (node (ref "U2") (pin "P$16") (pinfunction "VDD_P$16") (pintype "bidirectional"))
      (node (ref "U205") (pin "P$20") (pinfunction "P$20_P$20") (pintype "bidirectional"))
      (node (ref "U309") (pin "1") (pinfunction "P$1_1") (pintype "bidirectional"))
      (node (ref "U5") (pin "1") (pinfunction "VCC_1") (pintype "bidirectional"))
      (node (ref "U6") (pin "8") (pinfunction "+V_8") (pintype "power_in"))
      (node (ref "U7") (pin "7") (pinfunction "VCCB_7") (pintype "bidirectional"))
      (node (ref "U8") (pin "P$15") (pinfunction "15_LEDA_P$15") (pintype "bidirectional"))
      (node (ref "U8") (pin "P$2") (pinfunction "2_VDD_P$2") (pintype "bidirectional"))
    )
    (net (code "119") (name "VCC_5V_SERVO") (class "Default")
      (node (ref "C31") (pin "+") (pinfunction "+_+") (pintype "passive"))
      (node (ref "C58") (pin "2") (pinfunction "2_2") (pintype "passive"))
      (node (ref "C59") (pin "2") (pinfunction "2_2") (pintype "passive"))
      (node (ref "C60") (pin "2") (pinfunction "2_2") (pintype "passive"))
      (node (ref "D008") (pin "C") (pinfunction "C_C") (pintype "passive"))
      (node (ref "D3") (pin "-") (pinfunction "-_-") (pintype "passive"))
      (node (ref "J16") (pin "2") (pinfunction "V_2") (pintype "bidirectional"))
      (node (ref "J3") (pin "3") (pinfunction "3_3") (pintype "bidirectional"))
      (node (ref "P92") (pin "P$1") (pinfunction "P$1_P$1") (pintype "bidirectional"))
      (node (ref "R8") (pin "1") (pinfunction "1_1") (pintype "passive"))
    )
    (net (code "120") (name "VIN") (class "Default")
      (node (ref "C51") (pin "2") (pinfunction "2_2") (pintype "passive"))
      (node (ref "C53") (pin "2") (pinfunction "2_2") (pintype "passive"))
      (node (ref "C55") (pin "2") (pinfunction "2_2") (pintype "passive"))
      (node (ref "C56") (pin "2") (pinfunction "2_2") (pintype "passive"))
      (node (ref "D3") (pin "+") (pinfunction "+_+") (pintype "passive"))
      (node (ref "J4") (pin "1") (pinfunction "1_1") (pintype "bidirectional"))
      (node (ref "J8") (pin "1") (pinfunction "1_1") (pintype "bidirectional"))
      (node (ref "L3") (pin "1") (pinfunction "1_1") (pintype "passive"))
      (node (ref "L8") (pin "1") (pinfunction "1_1") (pintype "passive"))
      (node (ref "P2") (pin "P$1") (pinfunction "P$1_P$1") (pintype "bidirectional"))
      (node (ref "R13") (pin "2") (pinfunction "2_2") (pintype "passive"))
      (node (ref "R28") (pin "1") (pinfunction "1_1") (pintype "passive"))
      (node (ref "R31") (pin "2") (pinfunction "2_2") (pintype "passive"))
      (node (ref "U10") (pin "5") (pinfunction "VCC_5") (pintype "bidirectional"))
      (node (ref "U4") (pin "4") (pinfunction "EN_4") (pintype "bidirectional"))
      (node (ref "U4") (pin "5") (pinfunction "IN_5") (pintype "bidirectional"))
    )
    (net (code "121") (name "unconnected-(J3-Pad2)") (class "Default")
      (node (ref "J3") (pin "2") (pinfunction "2_2") (pintype "bidirectional"))
    )
    (net (code "122") (name "unconnected-(R23-2-Pad3)") (class "Default")
      (node (ref "R23") (pin "3") (pinfunction "2_3") (pintype "passive"))
    )
    (net (code "123") (name "unconnected-(U2-INT#-PadP$13)") (class "Default")
      (node (ref "U2") (pin "P$13") (pinfunction "INT#_P$13") (pintype "bidirectional"))
    )
    (net (code "124") (name "unconnected-(U3-INT1-Pad4)") (class "Default")
      (node (ref "U3") (pin "4") (pinfunction "INT1_4") (pintype "bidirectional"))
    )
    (net (code "125") (name "unconnected-(U3-INT2-Pad9)") (class "Default")
      (node (ref "U3") (pin "9") (pinfunction "INT2_9") (pintype "bidirectional"))
    )
    (net (code "126") (name "unconnected-(U4-NC-Pad6)") (class "Default")
      (node (ref "U4") (pin "6") (pinfunction "NC_6") (pintype "bidirectional"))
    )
    (net (code "127") (name "unconnected-(U8-7_D0-PadP$7)") (class "Default")
      (node (ref "U8") (pin "P$7") (pinfunction "7_D0_P$7") (pintype "bidirectional"))
    )
    (net (code "128") (name "unconnected-(U8-8_D1-PadP$8)") (class "Default")
      (node (ref "U8") (pin "P$8") (pinfunction "8_D1_P$8") (pintype "bidirectional"))
    )
    (net (code "129") (name "unconnected-(U8-9_D2-PadP$9)") (class "Default")
      (node (ref "U8") (pin "P$9") (pinfunction "9_D2_P$9") (pintype "bidirectional"))
    )
    (net (code "130") (name "unconnected-(U8-10_D3-PadP$10)") (class "Default")
      (node (ref "U8") (pin "P$10") (pinfunction "10_D3_P$10") (pintype "bidirectional"))
    )
    (net (code "131") (name "unconnected-(U10-OC-Pad6)") (class "Default")
      (node (ref "U10") (pin "6") (pinfunction "OC_6") (pintype "bidirectional"))
    )
    (net (code "132") (name "unconnected-(U205-PadP$4)") (class "Default")
      (node (ref "U205") (pin "P$4") (pinfunction "P$4_P$4") (pintype "bidirectional"))
    )
    (net (code "133") (name "unconnected-(U205-PadP$7)") (class "Default")
      (node (ref "U205") (pin "P$7") (pinfunction "P$7_P$7") (pintype "bidirectional"))
    )
    (net (code "134") (name "unconnected-(U205-PadP$8)") (class "Default")
      (node (ref "U205") (pin "P$8") (pinfunction "P$8_P$8") (pintype "bidirectional"))
    )
    (net (code "135") (name "unconnected-(U205-PadP$9)") (class "Default")
      (node (ref "U205") (pin "P$9") (pinfunction "P$9_P$9") (pintype "bidirectional"))
    )
  )
)
